# main_ver1_41.net
KiCad netlist of a schematic drawn in EAGLE
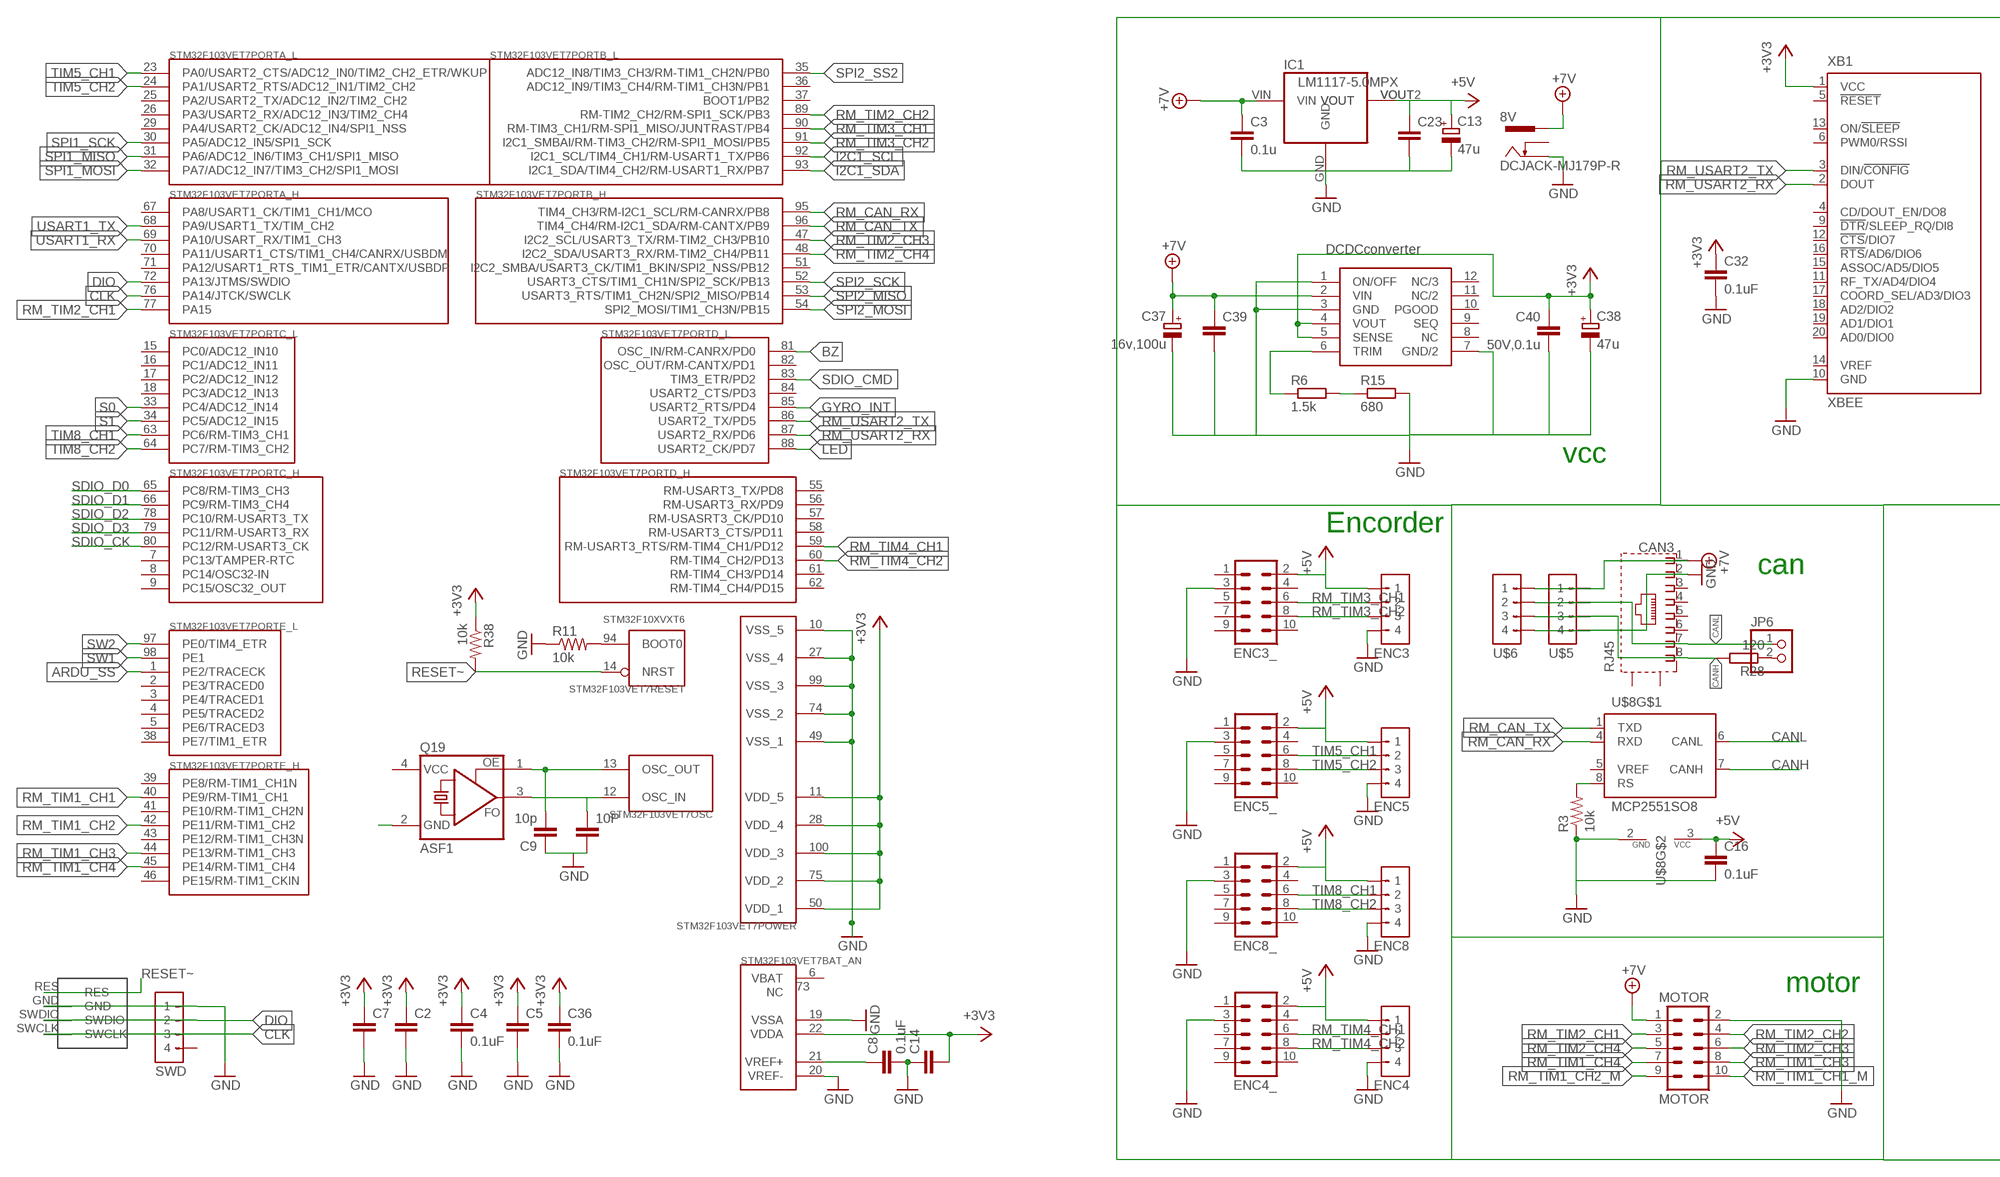
[diagram p0: schematic, sheet 1, part 1 of 2]
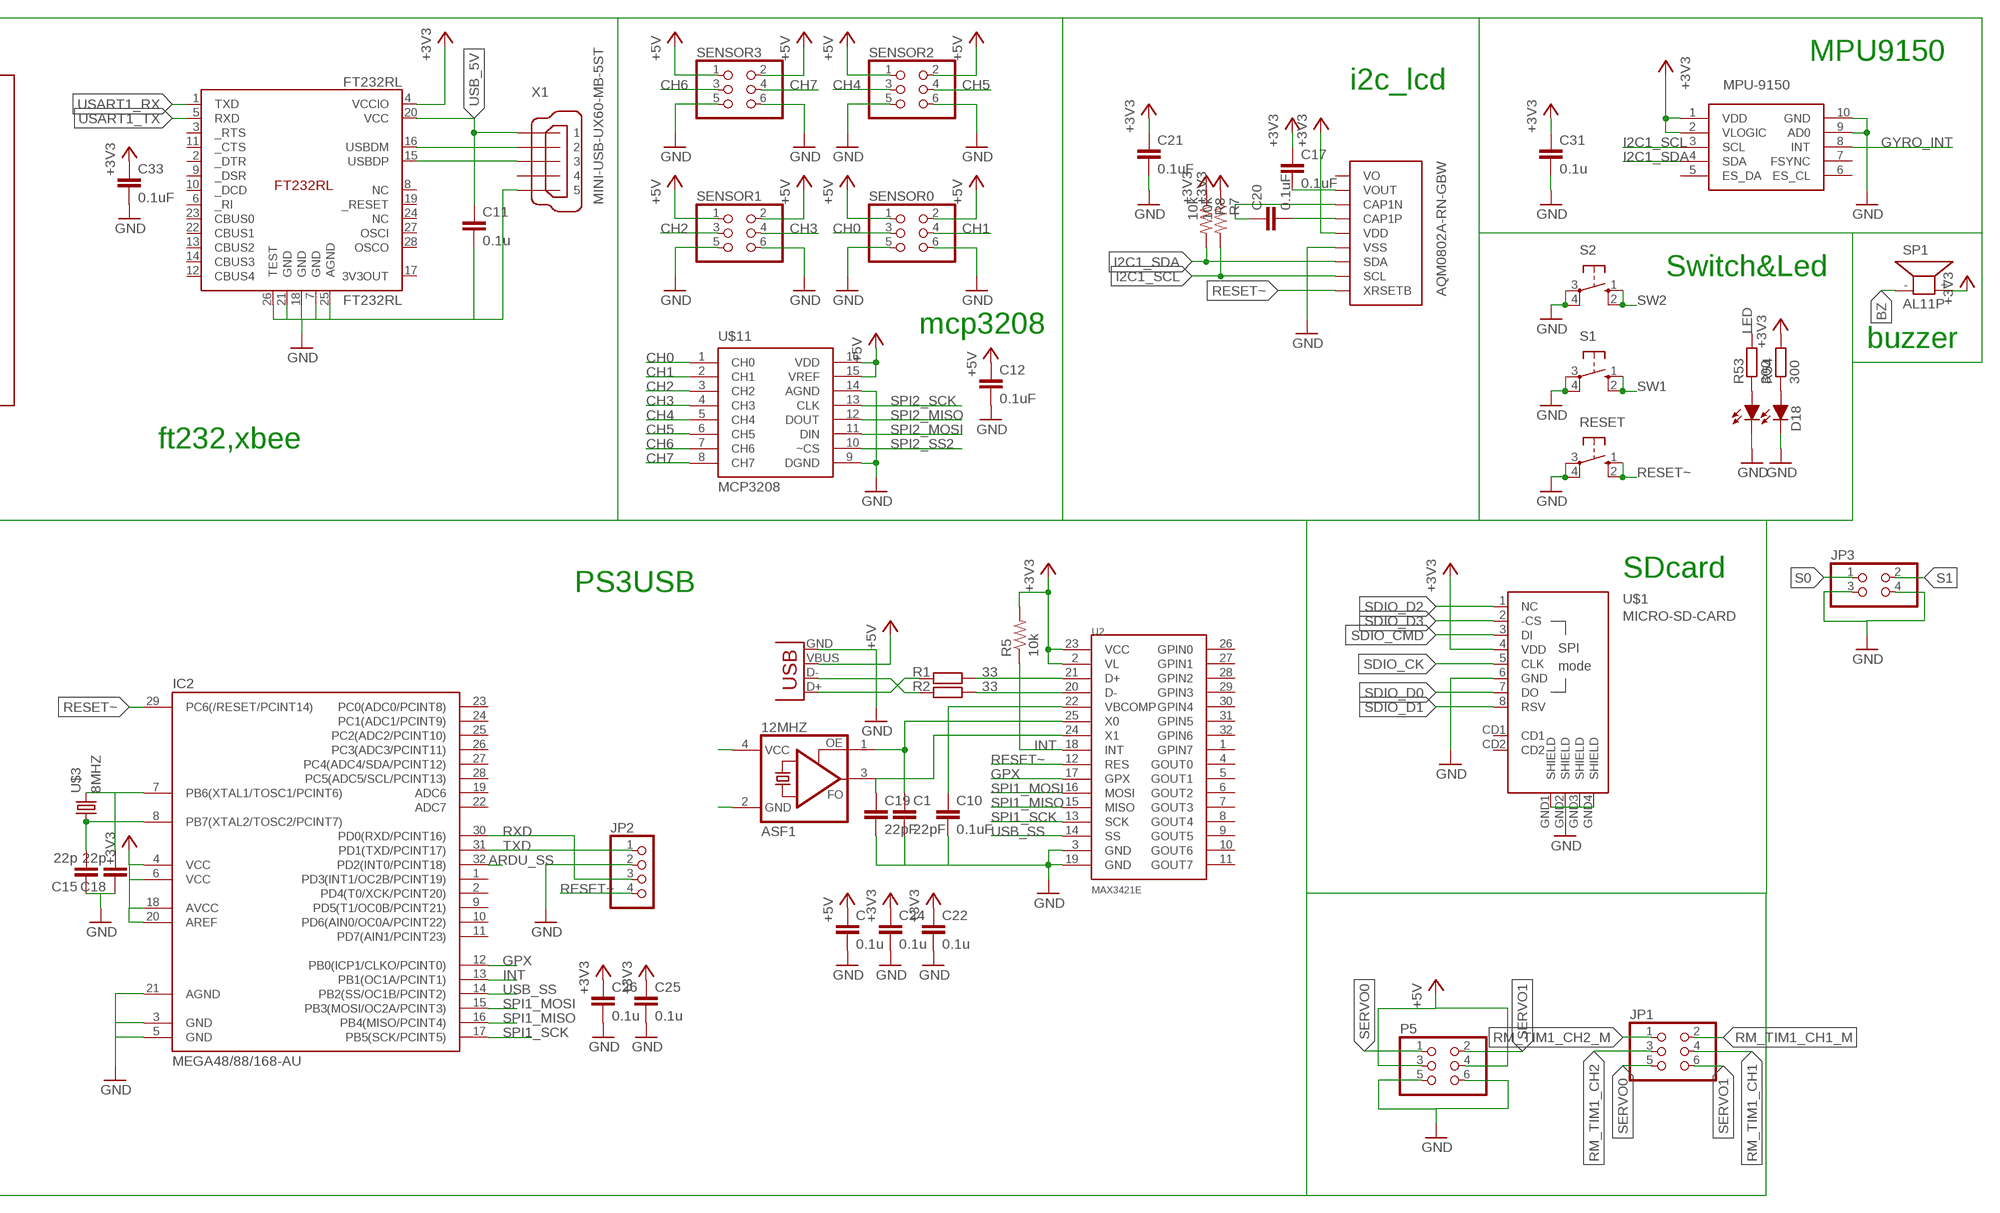
[diagram p1: schematic, sheet 1, part 2 of 2]

(export (version "E")
  (design (tool "Eeschema 10.0.6"))
  (components
    (comp (ref "8V")
      (value "DCJACK-MJ179P-R")
      (footprint "eagle-import:MJ-179P-R")
      (libsource (lib "eagle-import") (part "DCJACK-MJ179P-R"))
    )
    (comp (ref "10P")
      (value "C-EUC0603")
      (footprint "eagle-import:C0603")
      (libsource (lib "eagle-import") (part "C-EUC0603"))
    )
    (comp (ref "12MHZ")
      (value "ASF1")
      (footprint "eagle-import:ASF")
      (libsource (lib "eagle-import") (part "ASF1"))
    )
    (comp (ref "AQM0802A-RN-GBW")
      (value "AQM0802A-RN-GBW")
      (footprint "eagle-import:AQM0802")
      (libsource (lib "eagle-import") (part "AQM0802A-RN-GBW"))
    )
    (comp (ref "C")
      (value "0.1u")
      (footprint "eagle-import:C0603")
      (libsource (lib "eagle-import") (part "resistor_C-EUC0603"))
    )
    (comp (ref "C1")
      (value "22pF")
      (footprint "eagle-import:C0603K")
      (libsource (lib "eagle-import") (part "resistor_C-EUC0603K"))
    )
    (comp (ref "C2")
      (value "C-EUC0603")
      (footprint "eagle-import:C0603")
      (libsource (lib "eagle-import") (part "resistor_C-EUC0603"))
    )
    (comp (ref "C3")
      (value "0.1u")
      (footprint "eagle-import:C0603K")
      (libsource (lib "eagle-import") (part "resistor_C-EUC0603K"))
    )
    (comp (ref "C4")
      (value "0.1uF")
      (footprint "eagle-import:C0603")
      (libsource (lib "eagle-import") (part "resistor_C-EUC0603"))
    )
    (comp (ref "C5")
      (value "C-EUC0603")
      (footprint "eagle-import:C0603")
      (libsource (lib "eagle-import") (part "resistor_C-EUC0603"))
    )
    (comp (ref "C7")
      (value "C-EUC0603")
      (footprint "eagle-import:C0603")
      (libsource (lib "eagle-import") (part "resistor_C-EUC0603"))
    )
    (comp (ref "C8")
      (value "0.1uF")
      (footprint "eagle-import:C0603")
      (libsource (lib "eagle-import") (part "resistor_C-EUC0603"))
    )
    (comp (ref "C9")
      (value "10p")
      (footprint "eagle-import:C0603")
      (libsource (lib "eagle-import") (part "C-EUC0603"))
    )
    (comp (ref "C10")
      (value "0.1uF")
      (footprint "eagle-import:C0603K")
      (libsource (lib "eagle-import") (part "resistor_C-EUC0603K"))
    )
    (comp (ref "C11")
      (value "0.1u")
      (footprint "eagle-import:C0603K")
      (libsource (lib "eagle-import") (part "resistor_C-EUC0603K"))
    )
    (comp (ref "C12")
      (value "0.1uF")
      (footprint "eagle-import:C0603")
      (libsource (lib "eagle-import") (part "resistor_C-EUC0603"))
    )
    (comp (ref "C13")
      (value "47u")
      (footprint "eagle-import:153CLV-0405")
      (libsource (lib "eagle-import") (part "CPOL-EU153CLV-0405"))
    )
    (comp (ref "C14")
      (value "C-EUC0603")
      (footprint "eagle-import:C0603")
      (libsource (lib "eagle-import") (part "resistor_C-EUC0603"))
    )
    (comp (ref "C15")
      (value "22p")
      (footprint "eagle-import:C0603K")
      (libsource (lib "eagle-import") (part "resistor_C-EUC0603K"))
    )
    (comp (ref "C16")
      (value "0.1uF")
      (footprint "eagle-import:C0603")
      (libsource (lib "eagle-import") (part "resistor_C-EUC0603"))
    )
    (comp (ref "C17")
      (value "0.1uF")
      (footprint "eagle-import:C0603")
      (libsource (lib "eagle-import") (part "resistor_C-EUC0603"))
    )
    (comp (ref "C18")
      (value "22p")
      (footprint "eagle-import:C0603K")
      (libsource (lib "eagle-import") (part "resistor_C-EUC0603K"))
    )
    (comp (ref "C19")
      (value "22pF")
      (footprint "eagle-import:C0603K")
      (libsource (lib "eagle-import") (part "resistor_C-EUC0603K"))
    )
    (comp (ref "C20")
      (value "0.1uF")
      (footprint "eagle-import:C0603")
      (libsource (lib "eagle-import") (part "resistor_C-EUC0603"))
    )
    (comp (ref "C21")
      (value "0.1uF")
      (footprint "eagle-import:C0603")
      (libsource (lib "eagle-import") (part "resistor_C-EUC0603"))
    )
    (comp (ref "C22")
      (value "0.1u")
      (footprint "eagle-import:C0603")
      (libsource (lib "eagle-import") (part "resistor_C-EUC0603"))
    )
    (comp (ref "C23")
      (value "C-EUC0603K")
      (footprint "eagle-import:C0603K")
      (libsource (lib "eagle-import") (part "resistor_C-EUC0603K"))
    )
    (comp (ref "C24")
      (value "0.1u")
      (footprint "eagle-import:C0603")
      (libsource (lib "eagle-import") (part "resistor_C-EUC0603"))
    )
    (comp (ref "C25")
      (value "0.1u")
      (footprint "eagle-import:C0603")
      (libsource (lib "eagle-import") (part "resistor_C-EUC0603"))
    )
    (comp (ref "C26")
      (value "0.1u")
      (footprint "eagle-import:C0603")
      (libsource (lib "eagle-import") (part "resistor_C-EUC0603"))
    )
    (comp (ref "C31")
      (value "0.1u")
      (footprint "eagle-import:C0603K")
      (libsource (lib "eagle-import") (part "resistor_C-EUC0603K"))
    )
    (comp (ref "C32")
      (value "0.1uF")
      (footprint "eagle-import:C0603")
      (libsource (lib "eagle-import") (part "resistor_C-EUC0603"))
    )
    (comp (ref "C33")
      (value "0.1uF")
      (footprint "eagle-import:C0603")
      (libsource (lib "eagle-import") (part "resistor_C-EUC0603"))
    )
    (comp (ref "C36")
      (value "0.1uF")
      (footprint "eagle-import:C0603")
      (libsource (lib "eagle-import") (part "resistor_C-EUC0603"))
    )
    (comp (ref "C37")
      (value "16v,100u")
      (footprint "eagle-import:153CLV-0605")
      (libsource (lib "eagle-import") (part "CPOL-EU153CLV-0605"))
    )
    (comp (ref "C38")
      (value "47u")
      (footprint "eagle-import:153CLV-0405")
      (libsource (lib "eagle-import") (part "CPOL-EU153CLV-0405"))
    )
    (comp (ref "C39")
      (value "C-EUC0603K")
      (footprint "eagle-import:C0603K")
      (libsource (lib "eagle-import") (part "resistor_C-EUC0603K"))
    )
    (comp (ref "C40")
      (value "50V,0.1u")
      (footprint "eagle-import:C0603K")
      (libsource (lib "eagle-import") (part "resistor_C-EUC0603K"))
    )
    (comp (ref "CAN3")
      (value "RJ45")
      (footprint "eagle-import:LAN")
      (libsource (lib "eagle-import") (part "RJ45"))
    )
    (comp (ref "D18")
      (value "SEC2XX4")
      (footprint "eagle-import:LED3025")
      (libsource (lib "eagle-import") (part "SEC2XX4"))
    )
    (comp (ref "ENC3")
      (value "CN4-JST-XH-TOP")
      (footprint "eagle-import:JST-B4B-XH-A")
      (libsource (lib "eagle-import") (part "CN4-JST-XH-TOP"))
    )
    (comp (ref "ENC3_")
      (value "ML10L")
      (footprint "eagle-import:ML10L")
      (libsource (lib "eagle-import") (part "con-ml_ML10L"))
    )
    (comp (ref "ENC4")
      (value "CN4-JST-XH-TOP")
      (footprint "eagle-import:JST-B4B-XH-A")
      (libsource (lib "eagle-import") (part "CN4-JST-XH-TOP"))
    )
    (comp (ref "ENC4_")
      (value "ML10L")
      (footprint "eagle-import:ML10L")
      (libsource (lib "eagle-import") (part "con-ml_ML10L"))
    )
    (comp (ref "ENC5")
      (value "CN4-JST-XH-TOP")
      (footprint "eagle-import:JST-B4B-XH-A")
      (libsource (lib "eagle-import") (part "CN4-JST-XH-TOP"))
    )
    (comp (ref "ENC5_")
      (value "ML10L")
      (footprint "eagle-import:ML10L")
      (libsource (lib "eagle-import") (part "con-ml_ML10L"))
    )
    (comp (ref "ENC8")
      (value "CN4-JST-XH-TOP")
      (footprint "eagle-import:JST-B4B-XH-A")
      (libsource (lib "eagle-import") (part "CN4-JST-XH-TOP"))
    )
    (comp (ref "ENC8_")
      (value "ML10L")
      (footprint "eagle-import:ML10L")
      (libsource (lib "eagle-import") (part "con-ml_ML10L"))
    )
    (comp (ref "FT232RL")
      (value "FT232RL")
      (footprint "eagle-import:SSOP-28")
      (libsource (lib "eagle-import") (part "FT232RL"))
    )
    (comp (ref "IC1")
      (value "LM1117-5.0MPX")
      (footprint "eagle-import:SOT223")
      (libsource (lib "eagle-import") (part "LM1117IMP-5.0"))
    )
    (comp (ref "IC2")
      (value "MEGA48/88/168-AU")
      (footprint "eagle-import:TQFP32-08")
      (libsource (lib "eagle-import") (part "MEGA48/88/168-AU"))
    )
    (comp (ref "JP1")
      (value "PINHD-2X3")
      (footprint "eagle-import:2X03")
      (libsource (lib "eagle-import") (part "PINHD-2X3"))
    )
    (comp (ref "JP2")
      (value "PINHD-1X4")
      (footprint "eagle-import:1X04")
      (libsource (lib "eagle-import") (part "PINHD-1X4"))
    )
    (comp (ref "JP3")
      (value "PINHD-2X2/90")
      (footprint "eagle-import:2X02_90")
      (libsource (lib "eagle-import") (part "PINHD-2X2/90"))
    )
    (comp (ref "JP6")
      (value "PINHD-1X2")
      (footprint "eagle-import:1X02")
      (libsource (lib "eagle-import") (part "PINHD-1X2"))
    )
    (comp (ref "MOTOR")
      (value "MOTOR")
      (footprint "eagle-import:ML10L")
      (libsource (lib "eagle-import") (part "ML10L"))
    )
    (comp (ref "MPU9150")
      (value "MPU-9150")
      (footprint "eagle-import:MPU-9150")
      (libsource (lib "eagle-import") (part "MPU-9150"))
    )
    (comp (ref "P5")
      (value "PINHD-2X3/90")
      (footprint "eagle-import:2X03_90")
      (libsource (lib "eagle-import") (part "PINHD-2X3/90"))
    )
    (comp (ref "Q19")
      (value "ASF1")
      (footprint "eagle-import:ASF")
      (libsource (lib "eagle-import") (part "ASF1"))
    )
    (comp (ref "R1")
      (value "33")
      (footprint "eagle-import:R0603")
      (libsource (lib "eagle-import") (part "R-EU_R0603"))
    )
    (comp (ref "R2")
      (value "33")
      (footprint "eagle-import:R0603")
      (libsource (lib "eagle-import") (part "R-EU_R0603"))
    )
    (comp (ref "R3")
      (value "10k")
      (footprint "eagle-import:R0603")
      (libsource (lib "eagle-import") (part "R-US_R0603"))
    )
    (comp (ref "R5")
      (value "10k")
      (footprint "eagle-import:R0603")
      (libsource (lib "eagle-import") (part "R-US_R0603"))
    )
    (comp (ref "R6")
      (value "1.5k")
      (footprint "eagle-import:R0603")
      (libsource (lib "eagle-import") (part "R-EU_R0603"))
    )
    (comp (ref "R7")
      (value "10k")
      (footprint "eagle-import:R0603")
      (libsource (lib "eagle-import") (part "R-US_R0603"))
    )
    (comp (ref "R8")
      (value "10k")
      (footprint "eagle-import:R0603")
      (libsource (lib "eagle-import") (part "R-US_R0603"))
    )
    (comp (ref "R11")
      (value "10k")
      (footprint "eagle-import:R0603")
      (libsource (lib "eagle-import") (part "R-US_R0603"))
    )
    (comp (ref "R15")
      (value "680")
      (footprint "eagle-import:R0603")
      (libsource (lib "eagle-import") (part "R-EU_R0603"))
    )
    (comp (ref "R28")
      (value "120")
      (footprint "eagle-import:R0603")
      (libsource (lib "eagle-import") (part "R-EU_R0603"))
    )
    (comp (ref "R38")
      (value "10k")
      (footprint "eagle-import:R0603")
      (libsource (lib "eagle-import") (part "R-US_R0603"))
    )
    (comp (ref "R53")
      (value "300")
      (footprint "eagle-import:R0603")
      (libsource (lib "eagle-import") (part "R-EU_R0603"))
    )
    (comp (ref "R54")
      (value "300")
      (footprint "eagle-import:R0603")
      (libsource (lib "eagle-import") (part "R-EU_R0603"))
    )
    (comp (ref "RESET")
      (value "10-XX")
      (footprint "eagle-import:B3F-10XX")
      (fields (field (name "MPN") "B3F-1000"))
      (libsource (lib "eagle-import") (part "10-XX"))
    )
    (comp (ref "S1")
      (value "10-XX")
      (footprint "eagle-import:B3F-10XX")
      (fields (field (name "MPN") "B3F-1000"))
      (libsource (lib "eagle-import") (part "10-XX"))
    )
    (comp (ref "S2")
      (value "10-XX")
      (footprint "eagle-import:B3F-10XX")
      (fields (field (name "MPN") "B3F-1000"))
      (libsource (lib "eagle-import") (part "10-XX"))
    )
    (comp (ref "SENSOR0")
      (value "PINHD-2X3/90")
      (footprint "eagle-import:2X03_90")
      (libsource (lib "eagle-import") (part "PINHD-2X3/90"))
    )
    (comp (ref "SENSOR1")
      (value "PINHD-2X3/90")
      (footprint "eagle-import:2X03_90")
      (libsource (lib "eagle-import") (part "PINHD-2X3/90"))
    )
    (comp (ref "SENSOR2")
      (value "PINHD-2X3/90")
      (footprint "eagle-import:2X03_90")
      (libsource (lib "eagle-import") (part "PINHD-2X3/90"))
    )
    (comp (ref "SENSOR3")
      (value "PINHD-2X3/90")
      (footprint "eagle-import:2X03_90")
      (libsource (lib "eagle-import") (part "PINHD-2X3/90"))
    )
    (comp (ref "SP1")
      (value "AL11P")
      (footprint "eagle-import:AL11P")
      (libsource (lib "eagle-import") (part "AL11P"))
    )
    (comp (ref "STM32F103VET7")
      (value "STM32F10XVXT6")
      (footprint "eagle-import:LQFP100")
      (libsource (lib "eagle-import") (part "STM32F10XVXT6"))
    )
    (comp (ref "SWD")
      (value "TOP_TYPE_4PIN")
      (footprint "eagle-import:TOP_TYPE_4PIN")
      (libsource (lib "eagle-import") (part "TOP_TYPE_4PIN"))
    )
    (comp (ref "U$1")
      (value "MICRO-SD-CARD")
      (footprint "eagle-import:DM3AT-SF-PEJ")
      (libsource (lib "eagle-import") (part "MICRO-SD-CARD"))
    )
    (comp (ref "U$2")
      (value "OKL-T/6-W12N")
      (footprint "eagle-import:OKL-T_6-W12")
      (libsource (lib "eagle-import") (part "OKL-T/6-W12N"))
    )
    (comp (ref "U$3")
      (value "8MHZ")
      (footprint "eagle-import:8MHZ_C")
      (libsource (lib "eagle-import") (part "8MHZ"))
    )
    (comp (ref "U$5")
      (value "S4B-XH-SM4-TB")
      (footprint "eagle-import:S4B-XH-SM4-TB")
      (libsource (lib "eagle-import") (part "S4B-XH-SM4-TB"))
    )
    (comp (ref "U$6")
      (value "S4B-XH-SM4-TB")
      (footprint "eagle-import:S4B-XH-SM4-TB")
      (libsource (lib "eagle-import") (part "S4B-XH-SM4-TB"))
    )
    (comp (ref "U$7")
      (value "STRINK")
      (footprint "eagle-import:STLINK")
      (libsource (lib "eagle-import") (part "STRINK"))
    )
    (comp (ref "U$8")
      (value "MCP2551SO8")
      (footprint "eagle-import:SO08")
      (libsource (lib "eagle-import") (part "MCP2551SO8"))
    )
    (comp (ref "U$11")
      (value "MCP3208")
      (footprint "eagle-import:SO16")
      (libsource (lib "eagle-import") (part "MCP3208"))
    )
    (comp (ref "U2")
      (value "MAX3421E")
      (footprint "eagle-import:TQFP32-5MM")
      (libsource (lib "eagle-import") (part "MAX3421ESMD"))
    )
    (comp (ref "X1")
      (value "MINI-USB-UX60-MB-5ST")
      (footprint "eagle-import:UX60-MB-5ST")
      (libsource (lib "eagle-import") (part "MINI-USB-UX60-MB-5ST"))
    )
    (comp (ref "X2")
      (value "USB_")
      (footprint "eagle-import:USB-A-S-SILK-FEMALE")
      (libsource (lib "eagle-import") (part "USB_"))
    )
    (comp (ref "XB1")
      (value "XBEE")
      (footprint "eagle-import:XBEE")
      (libsource (lib "eagle-import") (part "XBEE"))
    )
  )
  (nets
    (net (code "1") (name "+3V3") (class "Default")
      (node (ref "AQM0802A-RN-GBW") (pin "P$5") (pinfunction "VDD_P$5") (pintype "bidirectional"))
      (node (ref "C14") (pin "2") (pinfunction "2_2") (pintype "passive"))
      (node (ref "C17") (pin "1") (pinfunction "1_1") (pintype "passive"))
      (node (ref "C2") (pin "1") (pinfunction "1_1") (pintype "passive"))
      (node (ref "C21") (pin "1") (pinfunction "1_1") (pintype "passive"))
      (node (ref "C22") (pin "1") (pinfunction "1_1") (pintype "passive"))
      (node (ref "C24") (pin "1") (pinfunction "1_1") (pintype "passive"))
      (node (ref "C25") (pin "1") (pinfunction "1_1") (pintype "passive"))
      (node (ref "C26") (pin "1") (pinfunction "1_1") (pintype "passive"))
      (node (ref "C31") (pin "1") (pinfunction "1_1") (pintype "passive"))
      (node (ref "C32") (pin "1") (pinfunction "1_1") (pintype "passive"))
      (node (ref "C33") (pin "1") (pinfunction "1_1") (pintype "passive"))
      (node (ref "C36") (pin "1") (pinfunction "1_1") (pintype "passive"))
      (node (ref "C38") (pin "+") (pinfunction "+_+") (pintype "passive"))
      (node (ref "C4") (pin "1") (pinfunction "1_1") (pintype "passive"))
      (node (ref "C40") (pin "1") (pinfunction "1_1") (pintype "passive"))
      (node (ref "C5") (pin "1") (pinfunction "1_1") (pintype "passive"))
      (node (ref "C7") (pin "1") (pinfunction "1_1") (pintype "passive"))
      (node (ref "FT232RL") (pin "4") (pinfunction "VCCIO_4") (pintype "power_in"))
      (node (ref "IC2") (pin "18") (pinfunction "AVCC_18") (pintype "passive"))
      (node (ref "IC2") (pin "20") (pinfunction "AREF_20") (pintype "passive"))
      (node (ref "IC2") (pin "4") (pinfunction "VCC_4") (pintype "power_in"))
      (node (ref "IC2") (pin "6") (pinfunction "VCC_6") (pintype "power_in"))
      (node (ref "MPU9150") (pin "1") (pinfunction "VDD_1") (pintype "bidirectional"))
      (node (ref "MPU9150") (pin "2") (pinfunction "VLOGIC_2") (pintype "bidirectional"))
      (node (ref "R38") (pin "1") (pinfunction "1_1") (pintype "passive"))
      (node (ref "R5") (pin "2") (pinfunction "2_2") (pintype "passive"))
      (node (ref "R54") (pin "2") (pinfunction "2_2") (pintype "passive"))
      (node (ref "R7") (pin "1") (pinfunction "1_1") (pintype "passive"))
      (node (ref "R8") (pin "1") (pinfunction "1_1") (pintype "passive"))
      (node (ref "SP1") (pin "+") (pinfunction "2_+") (pintype "passive"))
      (node (ref "STM32F103VET7") (pin "100") (pinfunction "VDD_3_100") (pintype "power_in"))
      (node (ref "STM32F103VET7") (pin "11") (pinfunction "VDD_5_11") (pintype "power_in"))
      (node (ref "STM32F103VET7") (pin "22") (pinfunction "VDDA_22") (pintype "power_in"))
      (node (ref "STM32F103VET7") (pin "28") (pinfunction "VDD_4_28") (pintype "power_in"))
      (node (ref "STM32F103VET7") (pin "50") (pinfunction "VDD_1_50") (pintype "power_in"))
      (node (ref "STM32F103VET7") (pin "75") (pinfunction "VDD_2_75") (pintype "power_in"))
      (node (ref "U$1") (pin "4") (pinfunction "VDD_4") (pintype "bidirectional"))
      (node (ref "U$2") (pin "4") (pinfunction "VOUT_4") (pintype "bidirectional"))
      (node (ref "U$2") (pin "5") (pinfunction "SENSE_5") (pintype "bidirectional"))
      (node (ref "U2") (pin "2") (pinfunction "VL_2") (pintype "bidirectional"))
      (node (ref "U2") (pin "23") (pinfunction "VCC_23") (pintype "bidirectional"))
      (node (ref "XB1") (pin "1") (pinfunction "VCC_1") (pintype "power_in"))
    )
    (net (code "2") (name "+5V") (class "Default")
      (node (ref "C") (pin "1") (pinfunction "1_1") (pintype "passive"))
      (node (ref "C12") (pin "1") (pinfunction "1_1") (pintype "passive"))
      (node (ref "C13") (pin "+") (pinfunction "+_+") (pintype "passive"))
      (node (ref "C16") (pin "1") (pinfunction "1_1") (pintype "passive"))
      (node (ref "C23") (pin "1") (pinfunction "1_1") (pintype "passive"))
      (node (ref "ENC3") (pin "1") (pinfunction "1_1") (pintype "passive"))
      (node (ref "ENC3_") (pin "2") (pinfunction "2_2") (pintype "passive"))
      (node (ref "ENC4") (pin "1") (pinfunction "1_1") (pintype "passive"))
      (node (ref "ENC4_") (pin "2") (pinfunction "2_2") (pintype "passive"))
      (node (ref "ENC5") (pin "1") (pinfunction "1_1") (pintype "passive"))
      (node (ref "ENC5_") (pin "2") (pinfunction "2_2") (pintype "passive"))
      (node (ref "ENC8") (pin "1") (pinfunction "1_1") (pintype "passive"))
      (node (ref "ENC8_") (pin "2") (pinfunction "2_2") (pintype "passive"))
      (node (ref "IC1") (pin "VOUT") (pinfunction "VOUT_VOUT") (pintype "output"))
      (node (ref "IC1") (pin "VOUT2") (pinfunction "VOUT_VOUT2") (pintype "output"))
      (node (ref "P5") (pin "3") (pinfunction "3_3") (pintype "passive"))
      (node (ref "P5") (pin "4") (pinfunction "4_4") (pintype "passive"))
      (node (ref "SENSOR0") (pin "1") (pinfunction "1_1") (pintype "passive"))
      (node (ref "SENSOR0") (pin "2") (pinfunction "2_2") (pintype "passive"))
      (node (ref "SENSOR1") (pin "1") (pinfunction "1_1") (pintype "passive"))
      (node (ref "SENSOR1") (pin "2") (pinfunction "2_2") (pintype "passive"))
      (node (ref "SENSOR2") (pin "1") (pinfunction "1_1") (pintype "passive"))
      (node (ref "SENSOR2") (pin "2") (pinfunction "2_2") (pintype "passive"))
      (node (ref "SENSOR3") (pin "1") (pinfunction "1_1") (pintype "passive"))
      (node (ref "SENSOR3") (pin "2") (pinfunction "2_2") (pintype "passive"))
      (node (ref "U$11") (pin "15") (pinfunction "VREF_15") (pintype "bidirectional"))
      (node (ref "U$11") (pin "16") (pinfunction "VDD_16") (pintype "bidirectional"))
      (node (ref "U$8") (pin "3") (pinfunction "VCC_3") (pintype "power_in"))
      (node (ref "X2") (pin "VBUS") (pinfunction "VBUS_VBUS") (pintype "bidirectional"))
    )
    (net (code "3") (name "+7V") (class "Default")
      (node (ref "8V") (pin "1") (pinfunction "1_1") (pintype "passive"))
      (node (ref "C3") (pin "1") (pinfunction "1_1") (pintype "passive"))
      (node (ref "C37") (pin "+") (pinfunction "+_+") (pintype "passive"))
      (node (ref "C39") (pin "1") (pinfunction "1_1") (pintype "passive"))
      (node (ref "CAN3") (pin "1") (pinfunction "1_1") (pintype "passive"))
      (node (ref "IC1") (pin "VIN") (pinfunction "VIN_VIN") (pintype "input"))
      (node (ref "MOTOR") (pin "1") (pinfunction "1_1") (pintype "passive"))
      (node (ref "U$2") (pin "2") (pinfunction "VIN_2") (pintype "bidirectional"))
      (node (ref "U$5") (pin "1") (pinfunction "1_1") (pintype "passive"))
      (node (ref "U$6") (pin "1") (pinfunction "1_1") (pintype "passive"))
    )
    (net (code "4") (name "/CH0") (class "Default")
      (node (ref "SENSOR0") (pin "3") (pinfunction "3_3") (pintype "passive"))
      (node (ref "U$11") (pin "1") (pinfunction "CH0_1") (pintype "bidirectional"))
    )
    (net (code "5") (name "/CH1") (class "Default")
      (node (ref "SENSOR0") (pin "4") (pinfunction "4_4") (pintype "passive"))
      (node (ref "U$11") (pin "2") (pinfunction "CH1_2") (pintype "bidirectional"))
    )
    (net (code "6") (name "/CH2") (class "Default")
      (node (ref "SENSOR1") (pin "3") (pinfunction "3_3") (pintype "passive"))
      (node (ref "U$11") (pin "3") (pinfunction "CH2_3") (pintype "bidirectional"))
    )
    (net (code "7") (name "/CH3") (class "Default")
      (node (ref "SENSOR1") (pin "4") (pinfunction "4_4") (pintype "passive"))
      (node (ref "U$11") (pin "4") (pinfunction "CH3_4") (pintype "bidirectional"))
    )
    (net (code "8") (name "/CH4") (class "Default")
      (node (ref "SENSOR2") (pin "3") (pinfunction "3_3") (pintype "passive"))
      (node (ref "U$11") (pin "5") (pinfunction "CH4_5") (pintype "bidirectional"))
    )
    (net (code "9") (name "/CH5") (class "Default")
      (node (ref "SENSOR2") (pin "4") (pinfunction "4_4") (pintype "passive"))
      (node (ref "U$11") (pin "6") (pinfunction "CH5_6") (pintype "bidirectional"))
    )
    (net (code "10") (name "/CH6") (class "Default")
      (node (ref "SENSOR3") (pin "3") (pinfunction "3_3") (pintype "passive"))
      (node (ref "U$11") (pin "7") (pinfunction "CH6_7") (pintype "bidirectional"))
    )
    (net (code "11") (name "/CH7") (class "Default")
      (node (ref "SENSOR3") (pin "4") (pinfunction "4_4") (pintype "passive"))
      (node (ref "U$11") (pin "8") (pinfunction "CH7_8") (pintype "bidirectional"))
    )
    (net (code "12") (name "/GPX") (class "Default")
      (node (ref "IC2") (pin "12") (pinfunction "PB0(ICP1/CLKO/PCINT0)_12") (pintype "bidirectional"))
      (node (ref "U2") (pin "17") (pinfunction "GPX_17") (pintype "bidirectional"))
    )
    (net (code "13") (name "/INT") (class "Default")
      (node (ref "IC2") (pin "13") (pinfunction "PB1(OC1A/PCINT1)_13") (pintype "bidirectional"))
      (node (ref "R5") (pin "1") (pinfunction "1_1") (pintype "passive"))
      (node (ref "U2") (pin "18") (pinfunction "INT_18") (pintype "bidirectional"))
    )
    (net (code "14") (name "/RESET~{}") (class "Default")
      (node (ref "AQM0802A-RN-GBW") (pin "P$9") (pinfunction "XRSETB_P$9") (pintype "bidirectional"))
      (node (ref "IC2") (pin "29") (pinfunction "PC6(/RESET/PCINT14)_29") (pintype "bidirectional"))
      (node (ref "JP2") (pin "4") (pinfunction "4_4") (pintype "passive"))
      (node (ref "R38") (pin "2") (pinfunction "2_2") (pintype "passive"))
      (node (ref "RESET") (pin "1") (pinfunction "S_1") (pintype "passive"))
      (node (ref "RESET") (pin "2") (pinfunction "S1_2") (pintype "passive"))
      (node (ref "STM32F103VET7") (pin "14") (pinfunction "NRST_14") (pintype "input"))
      (node (ref "U$7") (pin "RES") (pinfunction "RES_RES") (pintype "bidirectional"))
      (node (ref "U2") (pin "12") (pinfunction "RES_12") (pintype "bidirectional"))
    )
    (net (code "15") (name "/RXD") (class "Default")
      (node (ref "IC2") (pin "30") (pinfunction "PD0(RXD/PCINT16)_30") (pintype "bidirectional"))
      (node (ref "JP2") (pin "3") (pinfunction "3_3") (pintype "passive"))
    )
    (net (code "16") (name "/TXD") (class "Default")
      (node (ref "IC2") (pin "31") (pinfunction "PD1(TXD/PCINT17)_31") (pintype "bidirectional"))
      (node (ref "JP2") (pin "1") (pinfunction "1_1") (pintype "passive"))
    )
    (net (code "17") (name "/USB_SS") (class "Default")
      (node (ref "IC2") (pin "14") (pinfunction "PB2(SS/OC1B/PCINT2)_14") (pintype "bidirectional"))
      (node (ref "U2") (pin "14") (pinfunction "SS_14") (pintype "bidirectional"))
    )
    (net (code "18") (name "/VBAT") (class "Default")
      (node (ref "STM32F103VET7") (pin "6") (pinfunction "VBAT_6") (pintype "power_in"))
    )
    (net (code "19") (name "/VCC") (class "Default")
      (node (ref "Q19") (pin "4") (pinfunction "VCC_4") (pintype "power_in"))
    )
    (net (code "20") (name "ARDU_SS") (class "Default")
      (node (ref "IC2") (pin "32") (pinfunction "PD2(INT0/PCINT18)_32") (pintype "bidirectional"))
      (node (ref "STM32F103VET7") (pin "1") (pinfunction "PE2/TRACECK_1") (pintype "bidirectional"))
    )
    (net (code "21") (name "BZ") (class "Default")
      (node (ref "SP1") (pin "-") (pinfunction "1_-") (pintype "passive"))
      (node (ref "STM32F103VET7") (pin "81") (pinfunction "OSC_IN/RM-CANRX/PD0_81") (pintype "bidirectional"))
    )
    (net (code "22") (name "CANH") (class "Default")
      (node (ref "CAN3") (pin "8") (pinfunction "8_8") (pintype "passive"))
      (node (ref "R28") (pin "2") (pinfunction "2_2") (pintype "passive"))
      (node (ref "U$5") (pin "3") (pinfunction "3_3") (pintype "passive"))
      (node (ref "U$6") (pin "3") (pinfunction "3_3") (pintype "passive"))
      (node (ref "U$8") (pin "7") (pinfunction "CANH_7") (pintype "bidirectional"))
    )
    (net (code "23") (name "CANL") (class "Default")
      (node (ref "CAN3") (pin "7") (pinfunction "7_7") (pintype "passive"))
      (node (ref "JP6") (pin "1") (pinfunction "1_1") (pintype "passive"))
      (node (ref "U$5") (pin "2") (pinfunction "2_2") (pintype "passive"))
      (node (ref "U$6") (pin "2") (pinfunction "2_2") (pintype "passive"))
      (node (ref "U$8") (pin "6") (pinfunction "CANL_6") (pintype "bidirectional"))
    )
    (net (code "24") (name "CLK") (class "Default")
      (node (ref "STM32F103VET7") (pin "76") (pinfunction "PA14/JTCK/SWCLK_76") (pintype "bidirectional"))
      (node (ref "SWD") (pin "3") (pinfunction "3_3") (pintype "passive"))
      (node (ref "U$7") (pin "SWCLK") (pinfunction "SWCLK_SWCLK") (pintype "bidirectional"))
    )
    (net (code "25") (name "DIO") (class "Default")
      (node (ref "STM32F103VET7") (pin "72") (pinfunction "PA13/JTMS/SWDIO_72") (pintype "bidirectional"))
      (node (ref "SWD") (pin "2") (pinfunction "2_2") (pintype "passive"))
      (node (ref "U$7") (pin "SWDIO") (pinfunction "SWDIO_SWDIO") (pintype "bidirectional"))
    )
    (net (code "26") (name "GND") (class "Default")
      (node (ref "10P") (pin "2") (pinfunction "2_2") (pintype "passive"))
      (node (ref "8V") (pin "2") (pinfunction "2_2") (pintype "passive"))
      (node (ref "AQM0802A-RN-GBW") (pin "P$6") (pinfunction "VSS_P$6") (pintype "bidirectional"))
      (node (ref "C") (pin "2") (pinfunction "2_2") (pintype "passive"))
      (node (ref "C1") (pin "2") (pinfunction "2_2") (pintype "passive"))
      (node (ref "C10") (pin "2") (pinfunction "2_2") (pintype "passive"))
      (node (ref "C11") (pin "2") (pinfunction "2_2") (pintype "passive"))
      (node (ref "C12") (pin "2") (pinfunction "2_2") (pintype "passive"))
      (node (ref "C13") (pin "-") (pinfunction "-_-") (pintype "passive"))
      (node (ref "C14") (pin "1") (pinfunction "1_1") (pintype "passive"))
      (node (ref "C15") (pin "1") (pinfunction "1_1") (pintype "passive"))
      (node (ref "C16") (pin "2") (pinfunction "2_2") (pintype "passive"))
      (node (ref "C18") (pin "1") (pinfunction "1_1") (pintype "passive"))
      (node (ref "C19") (pin "2") (pinfunction "2_2") (pintype "passive"))
      (node (ref "C2") (pin "2") (pinfunction "2_2") (pintype "passive"))
      (node (ref "C21") (pin "2") (pinfunction "2_2") (pintype "passive"))
      (node (ref "C22") (pin "2") (pinfunction "2_2") (pintype "passive"))
      (node (ref "C23") (pin "2") (pinfunction "2_2") (pintype "passive"))
      (node (ref "C24") (pin "2") (pinfunction "2_2") (pintype "passive"))
      (node (ref "C25") (pin "2") (pinfunction "2_2") (pintype "passive"))
      (node (ref "C26") (pin "2") (pinfunction "2_2") (pintype "passive"))
      (node (ref "C3") (pin "2") (pinfunction "2_2") (pintype "passive"))
      (node (ref "C31") (pin "2") (pinfunction "2_2") (pintype "passive"))
      (node (ref "C32") (pin "2") (pinfunction "2_2") (pintype "passive"))
      (node (ref "C33") (pin "2") (pinfunction "2_2") (pintype "passive"))
      (node (ref "C36") (pin "2") (pinfunction "2_2") (pintype "passive"))
      (node (ref "C37") (pin "-") (pinfunction "-_-") (pintype "passive"))
      (node (ref "C38") (pin "-") (pinfunction "-_-") (pintype "passive"))
      (node (ref "C39") (pin "2") (pinfunction "2_2") (pintype "passive"))
      (node (ref "C4") (pin "2") (pinfunction "2_2") (pintype "passive"))
      (node (ref "C40") (pin "2") (pinfunction "2_2") (pintype "passive"))
      (node (ref "C5") (pin "2") (pinfunction "2_2") (pintype "passive"))
      (node (ref "C7") (pin "2") (pinfunction "2_2") (pintype "passive"))
      (node (ref "C8") (pin "2") (pinfunction "2_2") (pintype "passive"))
      (node (ref "C9") (pin "1") (pinfunction "1_1") (pintype "passive"))
      (node (ref "CAN3") (pin "2") (pinfunction "2_2") (pintype "passive"))
      (node (ref "D18") (pin "1") (pinfunction "C0_1") (pintype "passive"))
      (node (ref "D18") (pin "2") (pinfunction "C1_2") (pintype "passive"))
      (node (ref "ENC3") (pin "4") (pinfunction "4_4") (pintype "passive"))
      (node (ref "ENC3_") (pin "3") (pinfunction "3_3") (pintype "passive"))
      (node (ref "ENC4") (pin "4") (pinfunction "4_4") (pintype "passive"))
      (node (ref "ENC4_") (pin "3") (pinfunction "3_3") (pintype "passive"))
      (node (ref "ENC5") (pin "4") (pinfunction "4_4") (pintype "passive"))
      (node (ref "ENC5_") (pin "3") (pinfunction "3_3") (pintype "passive"))
      (node (ref "ENC8") (pin "4") (pinfunction "4_4") (pintype "passive"))
      (node (ref "ENC8_") (pin "3") (pinfunction "3_3") (pintype "passive"))
      (node (ref "FT232RL") (pin "18") (pinfunction "GND_18") (pintype "power_in"))
      (node (ref "FT232RL") (pin "21") (pinfunction "GND_21") (pintype "power_in"))
      (node (ref "FT232RL") (pin "25") (pinfunction "AGND_25") (pintype "power_in"))
      (node (ref "FT232RL") (pin "26") (pinfunction "TEST_26") (pintype "bidirectional"))
      (node (ref "FT232RL") (pin "7") (pinfunction "GND_7") (pintype "power_in"))
      (node (ref "IC1") (pin "GND") (pinfunction "GND_GND") (pintype "power_in"))
      (node (ref "IC2") (pin "21") (pinfunction "AGND_21") (pintype "power_in"))
      (node (ref "IC2") (pin "3") (pinfunction "GND_3") (pintype "power_in"))
      (node (ref "IC2") (pin "5") (pinfunction "GND_5") (pintype "power_in"))
      (node (ref "JP2") (pin "2") (pinfunction "2_2") (pintype "passive"))
      (node (ref "JP3") (pin "3") (pinfunction "3_3") (pintype "passive"))
      (node (ref "JP3") (pin "4") (pinfunction "4_4") (pintype "passive"))
      (node (ref "MOTOR") (pin "2") (pinfunction "2_2") (pintype "passive"))
      (node (ref "MPU9150") (pin "10") (pinfunction "GND_10") (pintype "bidirectional"))
      (node (ref "MPU9150") (pin "9") (pinfunction "AD0_9") (pintype "bidirectional"))
      (node (ref "P5") (pin "5") (pinfunction "5_5") (pintype "passive"))
      (node (ref "P5") (pin "6") (pinfunction "6_6") (pintype "passive"))
      (node (ref "R11") (pin "1") (pinfunction "1_1") (pintype "passive"))
      (node (ref "R15") (pin "2") (pinfunction "2_2") (pintype "passive"))
      (node (ref "R3") (pin "1") (pinfunction "1_1") (pintype "passive"))
      (node (ref "RESET") (pin "3") (pinfunction "P_3") (pintype "passive"))
      (node (ref "RESET") (pin "4") (pinfunction "P1_4") (pintype "passive"))
      (node (ref "S1") (pin "3") (pinfunction "P_3") (pintype "passive"))
      (node (ref "S1") (pin "4") (pinfunction "P1_4") (pintype "passive"))
      (node (ref "S2") (pin "3") (pinfunction "P_3") (pintype "passive"))
      (node (ref "S2") (pin "4") (pinfunction "P1_4") (pintype "passive"))
      (node (ref "SENSOR0") (pin "5") (pinfunction "5_5") (pintype "passive"))
      (node (ref "SENSOR0") (pin "6") (pinfunction "6_6") (pintype "passive"))
      (node (ref "SENSOR1") (pin "5") (pinfunction "5_5") (pintype "passive"))
      (node (ref "SENSOR1") (pin "6") (pinfunction "6_6") (pintype "passive"))
      (node (ref "SENSOR2") (pin "5") (pinfunction "5_5") (pintype "passive"))
      (node (ref "SENSOR2") (pin "6") (pinfunction "6_6") (pintype "passive"))
      (node (ref "SENSOR3") (pin "5") (pinfunction "5_5") (pintype "passive"))
      (node (ref "SENSOR3") (pin "6") (pinfunction "6_6") (pintype "passive"))
      (node (ref "STM32F103VET7") (pin "10") (pinfunction "VSS_5_10") (pintype "power_in"))
      (node (ref "STM32F103VET7") (pin "19") (pinfunction "VSSA_19") (pintype "power_in"))
      (node (ref "STM32F103VET7") (pin "20") (pinfunction "VREF-_20") (pintype "input"))
      (node (ref "STM32F103VET7") (pin "27") (pinfunction "VSS_4_27") (pintype "power_in"))
      (node (ref "STM32F103VET7") (pin "49") (pinfunction "VSS_1_49") (pintype "power_in"))
      (node (ref "STM32F103VET7") (pin "74") (pinfunction "VSS_2_74") (pintype "power_in"))
      (node (ref "STM32F103VET7") (pin "99") (pinfunction "VSS_3_99") (pintype "power_in"))
      (node (ref "SWD") (pin "1") (pinfunction "1_1") (pintype "passive"))
      (node (ref "U$1") (pin "6") (pinfunction "GND_6") (pintype "bidirectional"))
      (node (ref "U$1") (pin "GND1") (pinfunction "SHIELD_GND1") (pintype "bidirectional"))
      (node (ref "U$1") (pin "GND2") (pinfunction "SHIELD_GND2") (pintype "bidirectional"))
      (node (ref "U$1") (pin "GND3") (pinfunction "SHIELD_GND3") (pintype "bidirectional"))
      (node (ref "U$1") (pin "GND4") (pinfunction "SHIELD_GND4") (pintype "bidirectional"))
      (node (ref "U$11") (pin "14") (pinfunction "AGND_14") (pintype "bidirectional"))
      (node (ref "U$11") (pin "9") (pinfunction "DGND_9") (pintype "bidirectional"))
      (node (ref "U$2") (pin "1") (pinfunction "ON/OFF_1") (pintype "bidirectional"))
      (node (ref "U$2") (pin "3") (pinfunction "GND_3") (pintype "bidirectional"))
      (node (ref "U$2") (pin "7") (pinfunction "GND/2_7") (pintype "bidirectional"))
      (node (ref "U$5") (pin "4") (pinfunction "4_4") (pintype "passive"))
      (node (ref "U$6") (pin "4") (pinfunction "4_4") (pintype "passive"))
      (node (ref "U$7") (pin "GND") (pinfunction "GND_GND") (pintype "bidirectional"))
      (node (ref "U$8") (pin "2") (pinfunction "GND_2") (pintype "power_in"))
      (node (ref "U2") (pin "19") (pinfunction "GND_19") (pintype "bidirectional"))
      (node (ref "U2") (pin "3") (pinfunction "GND_3") (pintype "bidirectional"))
      (node (ref "X1") (pin "5") (pinfunction "5_5") (pintype "input"))
      (node (ref "X2") (pin "GND") (pinfunction "GND_GND") (pintype "bidirectional"))
      (node (ref "XB1") (pin "10") (pinfunction "GND_10") (pintype "power_in"))
    )
    (net (code "27") (name "GYRO_INT") (class "Default")
      (node (ref "MPU9150") (pin "8") (pinfunction "INT_8") (pintype "bidirectional"))
      (node (ref "STM32F103VET7") (pin "85") (pinfunction "USART2_RTS/PD4_85") (pintype "bidirectional"))
    )
    (net (code "28") (name "I2C1_SCL") (class "Default")
      (node (ref "AQM0802A-RN-GBW") (pin "P$8") (pinfunction "SCL_P$8") (pintype "bidirectional"))
      (node (ref "MPU9150") (pin "3") (pinfunction "SCL_3") (pintype "bidirectional"))
      (node (ref "R7") (pin "2") (pinfunction "2_2") (pintype "passive"))
      (node (ref "STM32F103VET7") (pin "92") (pinfunction "I2C1_SCL/TIM4_CH1/RM-USART1_TX/PB6_92") (pintype "bidirectional"))
    )
    (net (code "29") (name "I2C1_SDA") (class "Default")
      (node (ref "AQM0802A-RN-GBW") (pin "P$7") (pinfunction "SDA_P$7") (pintype "bidirectional"))
      (node (ref "MPU9150") (pin "4") (pinfunction "SDA_4") (pintype "bidirectional"))
      (node (ref "R8") (pin "2") (pinfunction "2_2") (pintype "passive"))
      (node (ref "STM32F103VET7") (pin "93") (pinfunction "I2C1_SDA/TIM4_CH2/RM-USART1_RX/PB7_93") (pintype "bidirectional"))
    )
    (net (code "30") (name "LED") (class "Default")
      (node (ref "R53") (pin "2") (pinfunction "2_2") (pintype "passive"))
      (node (ref "STM32F103VET7") (pin "88") (pinfunction "USART2_CK/PD7_88") (pintype "bidirectional"))
    )
    (net (code "31") (name "Net-(12MHZ-FO)") (class "Default")
      (node (ref "12MHZ") (pin "3") (pinfunction "FO_3") (pintype "output"))
      (node (ref "C19") (pin "1") (pinfunction "1_1") (pintype "passive"))
      (node (ref "U2") (pin "24") (pinfunction "X1_24") (pintype "bidirectional"))
    )
    (net (code "32") (name "Net-(12MHZ-OE)") (class "Default")
      (node (ref "12MHZ") (pin "1") (pinfunction "OE_1") (pintype "input"))
      (node (ref "C1") (pin "1") (pinfunction "1_1") (pintype "passive"))
      (node (ref "U2") (pin "25") (pinfunction "X0_25") (pintype "bidirectional"))
    )
    (net (code "33") (name "Net-(AQM0802A-RN-GBW-CAP1N)") (class "Default")
      (node (ref "AQM0802A-RN-GBW") (pin "P$3") (pinfunction "CAP1N_P$3") (pintype "bidirectional"))
      (node (ref "C20") (pin "1") (pinfunction "1_1") (pintype "passive"))
    )
    (net (code "34") (name "Net-(AQM0802A-RN-GBW-CAP1P)") (class "Default")
      (node (ref "AQM0802A-RN-GBW") (pin "P$4") (pinfunction "CAP1P_P$4") (pintype "bidirectional"))
      (node (ref "C20") (pin "2") (pinfunction "2_2") (pintype "passive"))
    )
    (net (code "35") (name "Net-(AQM0802A-RN-GBW-VOUT)") (class "Default")
      (node (ref "AQM0802A-RN-GBW") (pin "P$2") (pinfunction "VOUT_P$2") (pintype "bidirectional"))
      (node (ref "C17") (pin "2") (pinfunction "2_2") (pintype "passive"))
    )
    (net (code "36") (name "Net-(D18-A0)") (class "Default")
      (node (ref "D18") (pin "4") (pinfunction "A0_4") (pintype "passive"))
      (node (ref "R54") (pin "1") (pinfunction "1_1") (pintype "passive"))
    )
    (net (code "37") (name "Net-(D18-A1)") (class "Default")
      (node (ref "D18") (pin "3") (pinfunction "A1_3") (pintype "passive"))
      (node (ref "R53") (pin "1") (pinfunction "1_1") (pintype "passive"))
    )
    (net (code "38") (name "Net-(FT232RL-USBDM)") (class "Default")
      (node (ref "FT232RL") (pin "16") (pinfunction "USBDM_16") (pintype "bidirectional"))
      (node (ref "X1") (pin "2") (pinfunction "2_2") (pintype "input"))
    )
    (net (code "39") (name "Net-(FT232RL-USBDP)") (class "Default")
      (node (ref "FT232RL") (pin "15") (pinfunction "USBDP_15") (pintype "bidirectional"))
      (node (ref "X1") (pin "3") (pinfunction "3_3") (pintype "input"))
    )
    (net (code "40") (name "Net-(IC2-PB6(XTAL1{slash}TOSC1{slash}PCINT6))") (class "Default")
      (node (ref "C18") (pin "2") (pinfunction "2_2") (pintype "passive"))
      (node (ref "IC2") (pin "7") (pinfunction "PB6(XTAL1/TOSC1/PCINT6)_7") (pintype "bidirectional"))
      (node (ref "U$3") (pin "P$2") (pinfunction "2_P$2") (pintype "passive"))
    )
    (net (code "41") (name "Net-(IC2-PB7(XTAL2{slash}TOSC2{slash}PCINT7))") (class "Default")
      (node (ref "C15") (pin "2") (pinfunction "2_2") (pintype "passive"))
      (node (ref "IC2") (pin "8") (pinfunction "PB7(XTAL2/TOSC2/PCINT7)_8") (pintype "bidirectional"))
      (node (ref "U$3") (pin "P$1") (pinfunction "1_P$1") (pintype "passive"))
    )
    (net (code "42") (name "Net-(JP6-Pad2)") (class "Default")
      (node (ref "JP6") (pin "2") (pinfunction "2_2") (pintype "passive"))
      (node (ref "R28") (pin "1") (pinfunction "1_1") (pintype "passive"))
    )
    (net (code "43") (name "Net-(Q19-FO)") (class "Default")
      (node (ref "10P") (pin "1") (pinfunction "1_1") (pintype "passive"))
      (node (ref "Q19") (pin "3") (pinfunction "FO_3") (pintype "output"))
      (node (ref "STM32F103VET7") (pin "12") (pinfunction "OSC_IN_12") (pintype "input"))
    )
    (net (code "44") (name "Net-(Q19-OE)") (class "Default")
      (node (ref "C9") (pin "2") (pinfunction "2_2") (pintype "passive"))
      (node (ref "Q19") (pin "1") (pinfunction "OE_1") (pintype "input"))
      (node (ref "STM32F103VET7") (pin "13") (pinfunction "OSC_OUT_13") (pintype "output"))
    )
    (net (code "45") (name "Net-(R1-Pad2)") (class "Default")
      (node (ref "R1") (pin "2") (pinfunction "2_2") (pintype "passive"))
      (node (ref "X2") (pin "D+") (pinfunction "D+_D+") (pintype "bidirectional"))
    )
    (net (code "46") (name "Net-(R2-Pad2)") (class "Default")
      (node (ref "R2") (pin "2") (pinfunction "2_2") (pintype "passive"))
      (node (ref "X2") (pin "D-") (pinfunction "D-_D-") (pintype "bidirectional"))
    )
    (net (code "47") (name "Net-(R15-Pad1)") (class "Default")
      (node (ref "R15") (pin "1") (pinfunction "1_1") (pintype "passive"))
      (node (ref "R6") (pin "2") (pinfunction "2_2") (pintype "passive"))
    )
    (net (code "48") (name "Net-(STM32F103VET7A-VREF+)") (class "Default")
      (node (ref "C8") (pin "1") (pinfunction "1_1") (pintype "passive"))
      (node (ref "STM32F103VET7") (pin "21") (pinfunction "VREF+_21") (pintype "input"))
    )
    (net (code "49") (name "Net-(STM32F103VET7N-BOOT0)") (class "Default")
      (node (ref "R11") (pin "2") (pinfunction "2_2") (pintype "passive"))
      (node (ref "STM32F103VET7") (pin "94") (pinfunction "BOOT0_94") (pintype "input"))
    )
    (net (code "50") (name "Net-(U$2-TRIM)") (class "Default")
      (node (ref "R6") (pin "1") (pinfunction "1_1") (pintype "passive"))
      (node (ref "U$2") (pin "6") (pinfunction "TRIM_6") (pintype "bidirectional"))
    )
    (net (code "51") (name "Net-(U$8A-RS)") (class "Default")
      (node (ref "R3") (pin "2") (pinfunction "2_2") (pintype "passive"))
      (node (ref "U$8") (pin "8") (pinfunction "RS_8") (pintype "bidirectional"))
    )
    (net (code "52") (name "Net-(U2-D+)") (class "Default")
      (node (ref "R1") (pin "1") (pinfunction "1_1") (pintype "passive"))
      (node (ref "U2") (pin "21") (pinfunction "D+_21") (pintype "bidirectional"))
    )
    (net (code "53") (name "Net-(U2-D-)") (class "Default")
      (node (ref "R2") (pin "1") (pinfunction "1_1") (pintype "passive"))
      (node (ref "U2") (pin "20") (pinfunction "D-_20") (pintype "bidirectional"))
    )
    (net (code "54") (name "Net-(U2-VBCOMP)") (class "Default")
      (node (ref "C10") (pin "1") (pinfunction "1_1") (pintype "passive"))
      (node (ref "U2") (pin "22") (pinfunction "VBCOMP_22") (pintype "bidirectional"))
    )
    (net (code "55") (name "RM_CAN_RX") (class "Default")
      (node (ref "STM32F103VET7") (pin "95") (pinfunction "TIM4_CH3/RM-I2C1_SCL/RM-CANRX/PB8_95") (pintype "bidirectional"))
      (node (ref "U$8") (pin "4") (pinfunction "RXD_4") (pintype "bidirectional"))
    )
    (net (code "56") (name "RM_CAN_TX") (class "Default")
      (node (ref "STM32F103VET7") (pin "96") (pinfunction "TIM4_CH4/RM-I2C1_SDA/RM-CANTX/PB9_96") (pintype "bidirectional"))
      (node (ref "U$8") (pin "1") (pinfunction "TXD_1") (pintype "bidirectional"))
    )
    (net (code "57") (name "RM_TIM1_CH1") (class "Default")
      (node (ref "JP1") (pin "4") (pinfunction "4_4") (pintype "passive"))
      (node (ref "STM32F103VET7") (pin "40") (pinfunction "PE9/RM-TIM1_CH1_40") (pintype "bidirectional"))
    )
    (net (code "58") (name "RM_TIM1_CH1_M") (class "Default")
      (node (ref "JP1") (pin "2") (pinfunction "2_2") (pintype "passive"))
      (node (ref "MOTOR") (pin "10") (pinfunction "10_10") (pintype "passive"))
    )
    (net (code "59") (name "RM_TIM1_CH2") (class "Default")
      (node (ref "JP1") (pin "3") (pinfunction "3_3") (pintype "passive"))
      (node (ref "STM32F103VET7") (pin "42") (pinfunction "PE11/RM-TIM1_CH2_42") (pintype "bidirectional"))
    )
    (net (code "60") (name "RM_TIM1_CH2_M") (class "Default")
      (node (ref "JP1") (pin "1") (pinfunction "1_1") (pintype "passive"))
      (node (ref "MOTOR") (pin "9") (pinfunction "9_9") (pintype "passive"))
    )
    (net (code "61") (name "RM_TIM1_CH3") (class "Default")
      (node (ref "MOTOR") (pin "8") (pinfunction "8_8") (pintype "passive"))
      (node (ref "STM32F103VET7") (pin "44") (pinfunction "PE13/RM-TIM1_CH3_44") (pintype "bidirectional"))
    )
    (net (code "62") (name "RM_TIM1_CH4") (class "Default")
      (node (ref "MOTOR") (pin "7") (pinfunction "7_7") (pintype "passive"))
      (node (ref "STM32F103VET7") (pin "45") (pinfunction "PE14/RM-TIM1_CH4_45") (pintype "bidirectional"))
    )
    (net (code "63") (name "RM_TIM2_CH1") (class "Default")
      (node (ref "MOTOR") (pin "3") (pinfunction "3_3") (pintype "passive"))
      (node (ref "STM32F103VET7") (pin "77") (pinfunction "PA15_77") (pintype "bidirectional"))
    )
    (net (code "64") (name "RM_TIM2_CH2") (class "Default")
      (node (ref "MOTOR") (pin "4") (pinfunction "4_4") (pintype "passive"))
      (node (ref "STM32F103VET7") (pin "89") (pinfunction "RM-TIM2_CH2/RM-SPI1_SCK/PB3_89") (pintype "bidirectional"))
    )
    (net (code "65") (name "RM_TIM2_CH3") (class "Default")
      (node (ref "MOTOR") (pin "6") (pinfunction "6_6") (pintype "passive"))
      (node (ref "STM32F103VET7") (pin "47") (pinfunction "I2C2_SCL/USART3_TX/RM-TIM2_CH3/PB10_47") (pintype "bidirectional"))
    )
    (net (code "66") (name "RM_TIM2_CH4") (class "Default")
      (node (ref "MOTOR") (pin "5") (pinfunction "5_5") (pintype "passive"))
      (node (ref "STM32F103VET7") (pin "48") (pinfunction "I2C2_SDA/USART3_RX/RM-TIM2_CH4/PB11_48") (pintype "bidirectional"))
    )
    (net (code "67") (name "RM_TIM3_CH1") (class "Default")
      (node (ref "ENC3") (pin "2") (pinfunction "2_2") (pintype "passive"))
      (node (ref "ENC3_") (pin "6") (pinfunction "6_6") (pintype "passive"))
      (node (ref "STM32F103VET7") (pin "90") (pinfunction "RM-TIM3_CH1/RM-SPI1_MISO/JUNTRAST/PB4_90") (pintype "bidirectional"))
    )
    (net (code "68") (name "RM_TIM3_CH2") (class "Default")
      (node (ref "ENC3") (pin "3") (pinfunction "3_3") (pintype "passive"))
      (node (ref "ENC3_") (pin "8") (pinfunction "8_8") (pintype "passive"))
      (node (ref "STM32F103VET7") (pin "91") (pinfunction "I2C1_SMBAI/RM-TIM3_CH2/RM-SPI1_MOSI/PB5_91") (pintype "bidirectional"))
    )
    (net (code "69") (name "RM_TIM4_CH1") (class "Default")
      (node (ref "ENC4") (pin "2") (pinfunction "2_2") (pintype "passive"))
      (node (ref "ENC4_") (pin "6") (pinfunction "6_6") (pintype "passive"))
      (node (ref "STM32F103VET7") (pin "59") (pinfunction "RM-USART3_RTS/RM-TIM4_CH1/PD12_59") (pintype "bidirectional"))
    )
    (net (code "70") (name "RM_TIM4_CH2") (class "Default")
      (node (ref "ENC4") (pin "3") (pinfunction "3_3") (pintype "passive"))
      (node (ref "ENC4_") (pin "8") (pinfunction "8_8") (pintype "passive"))
      (node (ref "STM32F103VET7") (pin "60") (pinfunction "RM-TIM4_CH2/PD13_60") (pintype "bidirectional"))
    )
    (net (code "71") (name "RM_USART2_RX") (class "Default")
      (node (ref "STM32F103VET7") (pin "87") (pinfunction "USART2_RX/PD6_87") (pintype "bidirectional"))
      (node (ref "XB1") (pin "2") (pinfunction "DOUT_2") (pintype "output"))
    )
    (net (code "72") (name "RM_USART2_TX") (class "Default")
      (node (ref "STM32F103VET7") (pin "86") (pinfunction "USART2_TX/PD5_86") (pintype "bidirectional"))
      (node (ref "XB1") (pin "3") (pinfunction "DIN/~{CONFIG}_3") (pintype "input"))
    )
    (net (code "73") (name "S0") (class "Default")
      (node (ref "JP3") (pin "1") (pinfunction "1_1") (pintype "passive"))
      (node (ref "STM32F103VET7") (pin "33") (pinfunction "PC4/ADC12_IN14_33") (pintype "bidirectional"))
    )
    (net (code "74") (name "S1") (class "Default")
      (node (ref "JP3") (pin "2") (pinfunction "2_2") (pintype "passive"))
      (node (ref "STM32F103VET7") (pin "34") (pinfunction "PC5/ADC12_IN15_34") (pintype "bidirectional"))
    )
    (net (code "75") (name "SDIO_CK") (class "Default")
      (node (ref "STM32F103VET7") (pin "80") (pinfunction "PC12/RM-USART3_CK_80") (pintype "bidirectional"))
      (node (ref "U$1") (pin "5") (pinfunction "CLK_5") (pintype "bidirectional"))
    )
    (net (code "76") (name "SDIO_CMD") (class "Default")
      (node (ref "STM32F103VET7") (pin "83") (pinfunction "TIM3_ETR/PD2_83") (pintype "bidirectional"))
      (node (ref "U$1") (pin "3") (pinfunction "DI_3") (pintype "bidirectional"))
    )
    (net (code "77") (name "SDIO_D0") (class "Default")
      (node (ref "STM32F103VET7") (pin "65") (pinfunction "PC8/RM-TIM3_CH3_65") (pintype "bidirectional"))
      (node (ref "U$1") (pin "7") (pinfunction "DO_7") (pintype "bidirectional"))
    )
    (net (code "78") (name "SDIO_D1") (class "Default")
      (node (ref "STM32F103VET7") (pin "66") (pinfunction "PC9/RM-TIM3_CH4_66") (pintype "bidirectional"))
      (node (ref "U$1") (pin "8") (pinfunction "RSV_8") (pintype "bidirectional"))
    )
    (net (code "79") (name "SDIO_D2") (class "Default")
      (node (ref "STM32F103VET7") (pin "78") (pinfunction "PC10/RM-USART3_TX_78") (pintype "bidirectional"))
      (node (ref "U$1") (pin "1") (pinfunction "NC_1") (pintype "bidirectional"))
    )
    (net (code "80") (name "SDIO_D3") (class "Default")
      (node (ref "STM32F103VET7") (pin "79") (pinfunction "PC11/RM-USART3_RX_79") (pintype "bidirectional"))
      (node (ref "U$1") (pin "2") (pinfunction "-CS_2") (pintype "bidirectional"))
    )
    (net (code "81") (name "SERVO0") (class "Default")
      (node (ref "JP1") (pin "5") (pinfunction "5_5") (pintype "passive"))
      (node (ref "P5") (pin "1") (pinfunction "1_1") (pintype "passive"))
    )
    (net (code "82") (name "SERVO1") (class "Default")
      (node (ref "JP1") (pin "6") (pinfunction "6_6") (pintype "passive"))
      (node (ref "P5") (pin "2") (pinfunction "2_2") (pintype "passive"))
    )
    (net (code "83") (name "SPI1_MISO") (class "Default")
      (node (ref "IC2") (pin "16") (pinfunction "PB4(MISO/PCINT4)_16") (pintype "bidirectional"))
      (node (ref "STM32F103VET7") (pin "31") (pinfunction "PA6/ADC12_IN6/TIM3_CH1/SPI1_MISO_31") (pintype "bidirectional"))
      (node (ref "U2") (pin "15") (pinfunction "MISO_15") (pintype "bidirectional"))
    )
    (net (code "84") (name "SPI1_MOSI") (class "Default")
      (node (ref "IC2") (pin "15") (pinfunction "PB3(MOSI/OC2A/PCINT3)_15") (pintype "bidirectional"))
      (node (ref "STM32F103VET7") (pin "32") (pinfunction "PA7/ADC12_IN7/TIM3_CH2/SPI1_MOSI_32") (pintype "bidirectional"))
      (node (ref "U2") (pin "16") (pinfunction "MOSI_16") (pintype "bidirectional"))
    )
    (net (code "85") (name "SPI1_SCK") (class "Default")
      (node (ref "IC2") (pin "17") (pinfunction "PB5(SCK/PCINT5)_17") (pintype "bidirectional"))
      (node (ref "STM32F103VET7") (pin "30") (pinfunction "PA5/ADC12_IN5/SPI1_SCK_30") (pintype "bidirectional"))
      (node (ref "U2") (pin "13") (pinfunction "SCK_13") (pintype "bidirectional"))
    )
    (net (code "86") (name "SPI2_MISO") (class "Default")
      (node (ref "STM32F103VET7") (pin "53") (pinfunction "USART3_RTS/TIM1_CH2N/SPI2_MISO/PB14_53") (pintype "bidirectional"))
      (node (ref "U$11") (pin "12") (pinfunction "DOUT_12") (pintype "bidirectional"))
    )
    (net (code "87") (name "SPI2_MOSI") (class "Default")
      (node (ref "STM32F103VET7") (pin "54") (pinfunction "SPI2_MOSI/TIM1_CH3N/PB15_54") (pintype "bidirectional"))
      (node (ref "U$11") (pin "11") (pinfunction "DIN_11") (pintype "bidirectional"))
    )
    (net (code "88") (name "SPI2_SCK") (class "Default")
      (node (ref "STM32F103VET7") (pin "52") (pinfunction "USART3_CTS/TIM1_CH1N/SPI2_SCK/PB13_52") (pintype "bidirectional"))
      (node (ref "U$11") (pin "13") (pinfunction "CLK_13") (pintype "bidirectional"))
    )
    (net (code "89") (name "SPI2_SS2") (class "Default")
      (node (ref "STM32F103VET7") (pin "35") (pinfunction "ADC12_IN8/TIM3_CH3/RM-TIM1_CH2N/PB0_35") (pintype "bidirectional"))
      (node (ref "U$11") (pin "10") (pinfunction "~{CS}_10") (pintype "bidirectional"))
    )
    (net (code "90") (name "SW1") (class "Default")
      (node (ref "S1") (pin "1") (pinfunction "S_1") (pintype "passive"))
      (node (ref "S1") (pin "2") (pinfunction "S1_2") (pintype "passive"))
      (node (ref "STM32F103VET7") (pin "98") (pinfunction "PE1_98") (pintype "bidirectional"))
    )
    (net (code "91") (name "SW2") (class "Default")
      (node (ref "S2") (pin "1") (pinfunction "S_1") (pintype "passive"))
      (node (ref "S2") (pin "2") (pinfunction "S1_2") (pintype "passive"))
      (node (ref "STM32F103VET7") (pin "97") (pinfunction "PE0/TIM4_ETR_97") (pintype "bidirectional"))
    )
    (net (code "92") (name "TIM5_CH1") (class "Default")
      (node (ref "ENC5") (pin "2") (pinfunction "2_2") (pintype "passive"))
      (node (ref "ENC5_") (pin "6") (pinfunction "6_6") (pintype "passive"))
      (node (ref "STM32F103VET7") (pin "23") (pinfunction "PA0/USART2_CTS/ADC12_IN0/TIM2_CH2_ETR/WKUP_23") (pintype "bidirectional"))
    )
    (net (code "93") (name "TIM5_CH2") (class "Default")
      (node (ref "ENC5") (pin "3") (pinfunction "3_3") (pintype "passive"))
      (node (ref "ENC5_") (pin "8") (pinfunction "8_8") (pintype "passive"))
      (node (ref "STM32F103VET7") (pin "24") (pinfunction "PA1/USART2_RTS/ADC12_IN1/TIM2_CH2_24") (pintype "bidirectional"))
    )
    (net (code "94") (name "TIM8_CH1") (class "Default")
      (node (ref "ENC8") (pin "2") (pinfunction "2_2") (pintype "passive"))
      (node (ref "ENC8_") (pin "6") (pinfunction "6_6") (pintype "passive"))
      (node (ref "STM32F103VET7") (pin "63") (pinfunction "PC6/RM-TIM3_CH1_63") (pintype "bidirectional"))
    )
    (net (code "95") (name "TIM8_CH2") (class "Default")
      (node (ref "ENC8") (pin "3") (pinfunction "3_3") (pintype "passive"))
      (node (ref "ENC8_") (pin "8") (pinfunction "8_8") (pintype "passive"))
      (node (ref "STM32F103VET7") (pin "64") (pinfunction "PC7/RM-TIM3_CH2_64") (pintype "bidirectional"))
    )
    (net (code "96") (name "USART1_RX") (class "Default")
      (node (ref "FT232RL") (pin "1") (pinfunction "TXD_1") (pintype "output"))
      (node (ref "STM32F103VET7") (pin "69") (pinfunction "PA10/USART_RX/TIM1_CH3_69") (pintype "bidirectional"))
    )
    (net (code "97") (name "USART1_TX") (class "Default")
      (node (ref "FT232RL") (pin "5") (pinfunction "RXD_5") (pintype "input"))
      (node (ref "STM32F103VET7") (pin "68") (pinfunction "PA9/USART1_TX/TIM_CH2_68") (pintype "bidirectional"))
    )
    (net (code "98") (name "USB_5V") (class "Default")
      (node (ref "C11") (pin "1") (pinfunction "1_1") (pintype "passive"))
      (node (ref "FT232RL") (pin "20") (pinfunction "VCC_20") (pintype "power_in"))
      (node (ref "X1") (pin "1") (pinfunction "1_1") (pintype "input"))
    )
    (net (code "99") (name "unconnected-(8V-Pad3)") (class "Default")
      (node (ref "8V") (pin "3") (pinfunction "3_3") (pintype "passive"))
    )
    (net (code "100") (name "unconnected-(12MHZ-GND-Pad2)") (class "Default")
      (node (ref "12MHZ") (pin "2") (pinfunction "GND_2") (pintype "power_in"))
    )
    (net (code "101") (name "unconnected-(12MHZ-VCC-Pad4)") (class "Default")
      (node (ref "12MHZ") (pin "4") (pinfunction "VCC_4") (pintype "power_in"))
    )
    (net (code "102") (name "unconnected-(AQM0802A-RN-GBW-VO-PadP$1)") (class "Default")
      (node (ref "AQM0802A-RN-GBW") (pin "P$1") (pinfunction "VO_P$1") (pintype "bidirectional"))
    )
    (net (code "103") (name "unconnected-(CAN3-Pad3)") (class "Default")
      (node (ref "CAN3") (pin "3") (pinfunction "3_3") (pintype "passive"))
    )
    (net (code "104") (name "unconnected-(CAN3-Pad4)") (class "Default")
      (node (ref "CAN3") (pin "4") (pinfunction "4_4") (pintype "passive"))
    )
    (net (code "105") (name "unconnected-(CAN3-Pad5)") (class "Default")
      (node (ref "CAN3") (pin "5") (pinfunction "5_5") (pintype "passive"))
    )
    (net (code "106") (name "unconnected-(CAN3-Pad6)") (class "Default")
      (node (ref "CAN3") (pin "6") (pinfunction "6_6") (pintype "passive"))
    )
    (net (code "107") (name "unconnected-(CAN3-S-PadP$11)") (class "Default")
      (node (ref "CAN3") (pin "P$11") (pinfunction "S_P$11") (pintype "passive"))
    )
    (net (code "108") (name "unconnected-(CAN3-S-PadP$12)") (class "Default")
      (node (ref "CAN3") (pin "P$12") (pinfunction "S_P$12") (pintype "passive"))
    )
    (net (code "109") (name "unconnected-(ENC3_-Pad1)") (class "Default")
      (node (ref "ENC3_") (pin "1") (pinfunction "1_1") (pintype "passive"))
    )
    (net (code "110") (name "unconnected-(ENC3_-Pad4)") (class "Default")
      (node (ref "ENC3_") (pin "4") (pinfunction "4_4") (pintype "passive"))
    )
    (net (code "111") (name "unconnected-(ENC3_-Pad5)") (class "Default")
      (node (ref "ENC3_") (pin "5") (pinfunction "5_5") (pintype "passive"))
    )
    (net (code "112") (name "unconnected-(ENC3_-Pad7)") (class "Default")
      (node (ref "ENC3_") (pin "7") (pinfunction "7_7") (pintype "passive"))
    )
    (net (code "113") (name "unconnected-(ENC3_-Pad9)") (class "Default")
      (node (ref "ENC3_") (pin "9") (pinfunction "9_9") (pintype "passive"))
    )
    (net (code "114") (name "unconnected-(ENC3_-Pad10)") (class "Default")
      (node (ref "ENC3_") (pin "10") (pinfunction "10_10") (pintype "passive"))
    )
    (net (code "115") (name "unconnected-(ENC4_-Pad1)") (class "Default")
      (node (ref "ENC4_") (pin "1") (pinfunction "1_1") (pintype "passive"))
    )
    (net (code "116") (name "unconnected-(ENC4_-Pad4)") (class "Default")
      (node (ref "ENC4_") (pin "4") (pinfunction "4_4") (pintype "passive"))
    )
    (net (code "117") (name "unconnected-(ENC4_-Pad5)") (class "Default")
      (node (ref "ENC4_") (pin "5") (pinfunction "5_5") (pintype "passive"))
    )
    (net (code "118") (name "unconnected-(ENC4_-Pad7)") (class "Default")
      (node (ref "ENC4_") (pin "7") (pinfunction "7_7") (pintype "passive"))
    )
    (net (code "119") (name "unconnected-(ENC4_-Pad9)") (class "Default")
      (node (ref "ENC4_") (pin "9") (pinfunction "9_9") (pintype "passive"))
    )
    (net (code "120") (name "unconnected-(ENC4_-Pad10)") (class "Default")
      (node (ref "ENC4_") (pin "10") (pinfunction "10_10") (pintype "passive"))
    )
    (net (code "121") (name "unconnected-(ENC5_-Pad1)") (class "Default")
      (node (ref "ENC5_") (pin "1") (pinfunction "1_1") (pintype "passive"))
    )
    (net (code "122") (name "unconnected-(ENC5_-Pad4)") (class "Default")
      (node (ref "ENC5_") (pin "4") (pinfunction "4_4") (pintype "passive"))
    )
    (net (code "123") (name "unconnected-(ENC5_-Pad5)") (class "Default")
      (node (ref "ENC5_") (pin "5") (pinfunction "5_5") (pintype "passive"))
    )
    (net (code "124") (name "unconnected-(ENC5_-Pad7)") (class "Default")
      (node (ref "ENC5_") (pin "7") (pinfunction "7_7") (pintype "passive"))
    )
    (net (code "125") (name "unconnected-(ENC5_-Pad9)") (class "Default")
      (node (ref "ENC5_") (pin "9") (pinfunction "9_9") (pintype "passive"))
    )
    (net (code "126") (name "unconnected-(ENC5_-Pad10)") (class "Default")
      (node (ref "ENC5_") (pin "10") (pinfunction "10_10") (pintype "passive"))
    )
    (net (code "127") (name "unconnected-(ENC8_-Pad1)") (class "Default")
      (node (ref "ENC8_") (pin "1") (pinfunction "1_1") (pintype "passive"))
    )
    (net (code "128") (name "unconnected-(ENC8_-Pad4)") (class "Default")
      (node (ref "ENC8_") (pin "4") (pinfunction "4_4") (pintype "passive"))
    )
    (net (code "129") (name "unconnected-(ENC8_-Pad5)") (class "Default")
      (node (ref "ENC8_") (pin "5") (pinfunction "5_5") (pintype "passive"))
    )
    (net (code "130") (name "unconnected-(ENC8_-Pad7)") (class "Default")
      (node (ref "ENC8_") (pin "7") (pinfunction "7_7") (pintype "passive"))
    )
    (net (code "131") (name "unconnected-(ENC8_-Pad9)") (class "Default")
      (node (ref "ENC8_") (pin "9") (pinfunction "9_9") (pintype "passive"))
    )
    (net (code "132") (name "unconnected-(ENC8_-Pad10)") (class "Default")
      (node (ref "ENC8_") (pin "10") (pinfunction "10_10") (pintype "passive"))
    )
    (net (code "133") (name "unconnected-(FT232RL-3V3OUT-Pad17)") (class "Default")
      (node (ref "FT232RL") (pin "17") (pinfunction "3V3OUT_17") (pintype "output"))
    )
    (net (code "134") (name "unconnected-(FT232RL-CBUS0-Pad23)") (class "Default")
      (node (ref "FT232RL") (pin "23") (pinfunction "CBUS0_23") (pintype "bidirectional"))
    )
    (net (code "135") (name "unconnected-(FT232RL-CBUS1-Pad22)") (class "Default")
      (node (ref "FT232RL") (pin "22") (pinfunction "CBUS1_22") (pintype "bidirectional"))
    )
    (net (code "136") (name "unconnected-(FT232RL-CBUS2-Pad13)") (class "Default")
      (node (ref "FT232RL") (pin "13") (pinfunction "CBUS2_13") (pintype "bidirectional"))
    )
    (net (code "137") (name "unconnected-(FT232RL-CBUS3-Pad14)") (class "Default")
      (node (ref "FT232RL") (pin "14") (pinfunction "CBUS3_14") (pintype "bidirectional"))
    )
    (net (code "138") (name "unconnected-(FT232RL-CBUS4-Pad12)") (class "Default")
      (node (ref "FT232RL") (pin "12") (pinfunction "CBUS4_12") (pintype "bidirectional"))
    )
    (net (code "139") (name "unconnected-(FT232RL-NC-Pad8)") (class "Default")
      (node (ref "FT232RL") (pin "8") (pinfunction "NC_8") (pintype "no_connect"))
    )
    (net (code "140") (name "unconnected-(FT232RL-NC-Pad24)") (class "Default")
      (node (ref "FT232RL") (pin "24") (pinfunction "NC_24") (pintype "no_connect"))
    )
    (net (code "141") (name "unconnected-(FT232RL-OSCI-Pad27)") (class "Default")
      (node (ref "FT232RL") (pin "27") (pinfunction "OSCI_27") (pintype "input"))
    )
    (net (code "142") (name "unconnected-(FT232RL-OSCO-Pad28)") (class "Default")
      (node (ref "FT232RL") (pin "28") (pinfunction "OSCO_28") (pintype "output"))
    )
    (net (code "143") (name "unconnected-(FT232RL-_CTS-Pad11)") (class "Default")
      (node (ref "FT232RL") (pin "11") (pinfunction "_CTS_11") (pintype "input"))
    )
    (net (code "144") (name "unconnected-(FT232RL-_DCD-Pad10)") (class "Default")
      (node (ref "FT232RL") (pin "10") (pinfunction "_DCD_10") (pintype "input"))
    )
    (net (code "145") (name "unconnected-(FT232RL-_DSR-Pad9)") (class "Default")
      (node (ref "FT232RL") (pin "9") (pinfunction "_DSR_9") (pintype "input"))
    )
    (net (code "146") (name "unconnected-(FT232RL-_DTR-Pad2)") (class "Default")
      (node (ref "FT232RL") (pin "2") (pinfunction "_DTR_2") (pintype "input"))
    )
    (net (code "147") (name "unconnected-(FT232RL-_RESET-Pad19)") (class "Default")
      (node (ref "FT232RL") (pin "19") (pinfunction "_RESET_19") (pintype "input"))
    )
    (net (code "148") (name "unconnected-(FT232RL-_RI-Pad6)") (class "Default")
      (node (ref "FT232RL") (pin "6") (pinfunction "_RI_6") (pintype "input"))
    )
    (net (code "149") (name "unconnected-(FT232RL-_RTS-Pad3)") (class "Default")
      (node (ref "FT232RL") (pin "3") (pinfunction "_RTS_3") (pintype "output"))
    )
    (net (code "150") (name "unconnected-(IC2-ADC6-Pad19)") (class "Default")
      (node (ref "IC2") (pin "19") (pinfunction "ADC6_19") (pintype "passive"))
    )
    (net (code "151") (name "unconnected-(IC2-ADC7-Pad22)") (class "Default")
      (node (ref "IC2") (pin "22") (pinfunction "ADC7_22") (pintype "passive"))
    )
    (net (code "152") (name "unconnected-(IC2-PC0(ADC0{slash}PCINT8)-Pad23)") (class "Default")
      (node (ref "IC2") (pin "23") (pinfunction "PC0(ADC0/PCINT8)_23") (pintype "bidirectional"))
    )
    (net (code "153") (name "unconnected-(IC2-PC1(ADC1{slash}PCINT9)-Pad24)") (class "Default")
      (node (ref "IC2") (pin "24") (pinfunction "PC1(ADC1/PCINT9)_24") (pintype "bidirectional"))
    )
    (net (code "154") (name "unconnected-(IC2-PC2(ADC2{slash}PCINT10)-Pad25)") (class "Default")
      (node (ref "IC2") (pin "25") (pinfunction "PC2(ADC2/PCINT10)_25") (pintype "bidirectional"))
    )
    (net (code "155") (name "unconnected-(IC2-PC3(ADC3{slash}PCINT11)-Pad26)") (class "Default")
      (node (ref "IC2") (pin "26") (pinfunction "PC3(ADC3/PCINT11)_26") (pintype "bidirectional"))
    )
    (net (code "156") (name "unconnected-(IC2-PC4(ADC4{slash}SDA{slash}PCINT12)-Pad27)") (class "Default")
      (node (ref "IC2") (pin "27") (pinfunction "PC4(ADC4/SDA/PCINT12)_27") (pintype "bidirectional"))
    )
    (net (code "157") (name "unconnected-(IC2-PC5(ADC5{slash}SCL{slash}PCINT13)-Pad28)") (class "Default")
      (node (ref "IC2") (pin "28") (pinfunction "PC5(ADC5/SCL/PCINT13)_28") (pintype "bidirectional"))
    )
    (net (code "158") (name "unconnected-(IC2-PD3(INT1{slash}OC2B{slash}PCINT19)-Pad1)") (class "Default")
      (node (ref "IC2") (pin "1") (pinfunction "PD3(INT1/OC2B/PCINT19)_1") (pintype "bidirectional"))
    )
    (net (code "159") (name "unconnected-(IC2-PD4(T0{slash}XCK{slash}PCINT20)-Pad2)") (class "Default")
      (node (ref "IC2") (pin "2") (pinfunction "PD4(T0/XCK/PCINT20)_2") (pintype "bidirectional"))
    )
    (net (code "160") (name "unconnected-(IC2-PD5(T1{slash}OC0B{slash}PCINT21)-Pad9)") (class "Default")
      (node (ref "IC2") (pin "9") (pinfunction "PD5(T1/OC0B/PCINT21)_9") (pintype "bidirectional"))
    )
    (net (code "161") (name "unconnected-(IC2-PD6(AIN0{slash}OC0A{slash}PCINT22)-Pad10)") (class "Default")
      (node (ref "IC2") (pin "10") (pinfunction "PD6(AIN0/OC0A/PCINT22)_10") (pintype "bidirectional"))
    )
    (net (code "162") (name "unconnected-(IC2-PD7(AIN1{slash}PCINT23)-Pad11)") (class "Default")
      (node (ref "IC2") (pin "11") (pinfunction "PD7(AIN1/PCINT23)_11") (pintype "bidirectional"))
    )
    (net (code "163") (name "unconnected-(MPU9150-ES_CL-Pad6)") (class "Default")
      (node (ref "MPU9150") (pin "6") (pinfunction "ES_CL_6") (pintype "bidirectional"))
    )
    (net (code "164") (name "unconnected-(MPU9150-ES_DA-Pad5)") (class "Default")
      (node (ref "MPU9150") (pin "5") (pinfunction "ES_DA_5") (pintype "bidirectional"))
    )
    (net (code "165") (name "unconnected-(MPU9150-FSYNC-Pad7)") (class "Default")
      (node (ref "MPU9150") (pin "7") (pinfunction "FSYNC_7") (pintype "bidirectional"))
    )
    (net (code "166") (name "unconnected-(Q19-GND-Pad2)") (class "Default")
      (node (ref "Q19") (pin "2") (pinfunction "GND_2") (pintype "power_in"))
    )
    (net (code "167") (name "unconnected-(STM32F103VET7A-NC-Pad73)") (class "Default")
      (node (ref "STM32F103VET7") (pin "73") (pinfunction "NC_73") (pintype "no_connect"))
    )
    (net (code "168") (name "unconnected-(STM32F103VET7C-PA8{slash}USART1_CK{slash}TIM1_CH1{slash}MCO-Pad67)") (class "Default")
      (node (ref "STM32F103VET7") (pin "67") (pinfunction "PA8/USART1_CK/TIM1_CH1/MCO_67") (pintype "bidirectional"))
    )
    (net (code "169") (name "unconnected-(STM32F103VET7C-PA11{slash}USART1_CTS{slash}TIM1_CH4{slash}CANRX{slash}USBDM-Pad70)") (class "Default")
      (node (ref "STM32F103VET7") (pin "70") (pinfunction "PA11/USART1_CTS/TIM1_CH4/CANRX/USBDM_70") (pintype "bidirectional"))
    )
    (net (code "170") (name "unconnected-(STM32F103VET7C-PA12{slash}USART1_RTS_TIM1_ETR{slash}CANTX{slash}USBDP-Pad71)") (class "Default")
      (node (ref "STM32F103VET7") (pin "71") (pinfunction "PA12/USART1_RTS_TIM1_ETR/CANTX/USBDP_71") (pintype "bidirectional"))
    )
    (net (code "171") (name "unconnected-(STM32F103VET7D-PA2{slash}USART2_TX{slash}ADC12_IN2{slash}TIM2_CH2-Pad25)") (class "Default")
      (node (ref "STM32F103VET7") (pin "25") (pinfunction "PA2/USART2_TX/ADC12_IN2/TIM2_CH2_25") (pintype "bidirectional"))
    )
    (net (code "172") (name "unconnected-(STM32F103VET7D-PA3{slash}USART2_RX{slash}ADC12_IN3{slash}TIM2_CH4-Pad26)") (class "Default")
      (node (ref "STM32F103VET7") (pin "26") (pinfunction "PA3/USART2_RX/ADC12_IN3/TIM2_CH4_26") (pintype "bidirectional"))
    )
    (net (code "173") (name "unconnected-(STM32F103VET7D-PA4{slash}USART2_CK{slash}ADC12_IN4{slash}SPI1_NSS-Pad29)") (class "Default")
      (node (ref "STM32F103VET7") (pin "29") (pinfunction "PA4/USART2_CK/ADC12_IN4/SPI1_NSS_29") (pintype "bidirectional"))
    )
    (net (code "174") (name "unconnected-(STM32F103VET7E-I2C2_SMBA{slash}USART3_CK{slash}TIM1_BKIN{slash}SPI2_NSS{slash}PB12-Pad51)") (class "Default")
      (node (ref "STM32F103VET7") (pin "51") (pinfunction "I2C2_SMBA/USART3_CK/TIM1_BKIN/SPI2_NSS/PB12_51") (pintype "bidirectional"))
    )
    (net (code "175") (name "unconnected-(STM32F103VET7F-ADC12_IN9{slash}TIM3_CH4{slash}RM-TIM1_CH3N{slash}PB1-Pad36)") (class "Default")
      (node (ref "STM32F103VET7") (pin "36") (pinfunction "ADC12_IN9/TIM3_CH4/RM-TIM1_CH3N/PB1_36") (pintype "bidirectional"))
    )
    (net (code "176") (name "unconnected-(STM32F103VET7F-BOOT1{slash}PB2-Pad37)") (class "Default")
      (node (ref "STM32F103VET7") (pin "37") (pinfunction "BOOT1/PB2_37") (pintype "bidirectional"))
    )
    (net (code "177") (name "unconnected-(STM32F103VET7G-PC13{slash}TAMPER-RTC-Pad7)") (class "Default")
      (node (ref "STM32F103VET7") (pin "7") (pinfunction "PC13/TAMPER-RTC_7") (pintype "bidirectional"))
    )
    (net (code "178") (name "unconnected-(STM32F103VET7G-PC14{slash}OSC32-IN-Pad8)") (class "Default")
      (node (ref "STM32F103VET7") (pin "8") (pinfunction "PC14/OSC32-IN_8") (pintype "bidirectional"))
    )
    (net (code "179") (name "unconnected-(STM32F103VET7G-PC15{slash}OSC32_OUT-Pad9)") (class "Default")
      (node (ref "STM32F103VET7") (pin "9") (pinfunction "PC15/OSC32_OUT_9") (pintype "bidirectional"))
    )
    (net (code "180") (name "unconnected-(STM32F103VET7H-PC0{slash}ADC12_IN10-Pad15)") (class "Default")
      (node (ref "STM32F103VET7") (pin "15") (pinfunction "PC0/ADC12_IN10_15") (pintype "bidirectional"))
    )
    (net (code "181") (name "unconnected-(STM32F103VET7H-PC1{slash}ADC12_IN11-Pad16)") (class "Default")
      (node (ref "STM32F103VET7") (pin "16") (pinfunction "PC1/ADC12_IN11_16") (pintype "bidirectional"))
    )
    (net (code "182") (name "unconnected-(STM32F103VET7H-PC2{slash}ADC12_IN12-Pad17)") (class "Default")
      (node (ref "STM32F103VET7") (pin "17") (pinfunction "PC2/ADC12_IN12_17") (pintype "bidirectional"))
    )
    (net (code "183") (name "unconnected-(STM32F103VET7H-PC3{slash}ADC12_IN13-Pad18)") (class "Default")
      (node (ref "STM32F103VET7") (pin "18") (pinfunction "PC3/ADC12_IN13_18") (pintype "bidirectional"))
    )
    (net (code "184") (name "unconnected-(STM32F103VET7I-RM-TIM4_CH3{slash}PD14-Pad61)") (class "Default")
      (node (ref "STM32F103VET7") (pin "61") (pinfunction "RM-TIM4_CH3/PD14_61") (pintype "bidirectional"))
    )
    (net (code "185") (name "unconnected-(STM32F103VET7I-RM-TIM4_CH4{slash}PD15-Pad62)") (class "Default")
      (node (ref "STM32F103VET7") (pin "62") (pinfunction "RM-TIM4_CH4/PD15_62") (pintype "bidirectional"))
    )
    (net (code "186") (name "unconnected-(STM32F103VET7I-RM-USART3_CTS{slash}PD11-Pad58)") (class "Default")
      (node (ref "STM32F103VET7") (pin "58") (pinfunction "RM-USART3_CTS/PD11_58") (pintype "bidirectional"))
    )
    (net (code "187") (name "unconnected-(STM32F103VET7I-RM-USART3_RX{slash}PD9-Pad56)") (class "Default")
      (node (ref "STM32F103VET7") (pin "56") (pinfunction "RM-USART3_RX/PD9_56") (pintype "bidirectional"))
    )
    (net (code "188") (name "unconnected-(STM32F103VET7I-RM-USART3_TX{slash}PD8-Pad55)") (class "Default")
      (node (ref "STM32F103VET7") (pin "55") (pinfunction "RM-USART3_TX/PD8_55") (pintype "bidirectional"))
    )
    (net (code "189") (name "unconnected-(STM32F103VET7I-RM-USASRT3_CK{slash}PD10-Pad57)") (class "Default")
      (node (ref "STM32F103VET7") (pin "57") (pinfunction "RM-USASRT3_CK/PD10_57") (pintype "bidirectional"))
    )
    (net (code "190") (name "unconnected-(STM32F103VET7J-OSC_OUT{slash}RM-CANTX{slash}PD1-Pad82)") (class "Default")
      (node (ref "STM32F103VET7") (pin "82") (pinfunction "OSC_OUT/RM-CANTX/PD1_82") (pintype "bidirectional"))
    )
    (net (code "191") (name "unconnected-(STM32F103VET7J-USART2_CTS{slash}PD3-Pad84)") (class "Default")
      (node (ref "STM32F103VET7") (pin "84") (pinfunction "USART2_CTS/PD3_84") (pintype "bidirectional"))
    )
    (net (code "192") (name "unconnected-(STM32F103VET7K-PE8{slash}RM-TIM1_CH1N-Pad39)") (class "Default")
      (node (ref "STM32F103VET7") (pin "39") (pinfunction "PE8/RM-TIM1_CH1N_39") (pintype "bidirectional"))
    )
    (net (code "193") (name "unconnected-(STM32F103VET7K-PE10{slash}RM-TIM1_CH2N-Pad41)") (class "Default")
      (node (ref "STM32F103VET7") (pin "41") (pinfunction "PE10/RM-TIM1_CH2N_41") (pintype "bidirectional"))
    )
    (net (code "194") (name "unconnected-(STM32F103VET7K-PE12{slash}RM-TIM1_CH3N-Pad43)") (class "Default")
      (node (ref "STM32F103VET7") (pin "43") (pinfunction "PE12/RM-TIM1_CH3N_43") (pintype "bidirectional"))
    )
    (net (code "195") (name "unconnected-(STM32F103VET7K-PE15{slash}RM-TIM1_CKIN-Pad46)") (class "Default")
      (node (ref "STM32F103VET7") (pin "46") (pinfunction "PE15/RM-TIM1_CKIN_46") (pintype "bidirectional"))
    )
    (net (code "196") (name "unconnected-(STM32F103VET7L-PE3{slash}TRACED0-Pad2)") (class "Default")
      (node (ref "STM32F103VET7") (pin "2") (pinfunction "PE3/TRACED0_2") (pintype "bidirectional"))
    )
    (net (code "197") (name "unconnected-(STM32F103VET7L-PE4{slash}TRACED1-Pad3)") (class "Default")
      (node (ref "STM32F103VET7") (pin "3") (pinfunction "PE4/TRACED1_3") (pintype "bidirectional"))
    )
    (net (code "198") (name "unconnected-(STM32F103VET7L-PE5{slash}TRACED2-Pad4)") (class "Default")
      (node (ref "STM32F103VET7") (pin "4") (pinfunction "PE5/TRACED2_4") (pintype "bidirectional"))
    )
    (net (code "199") (name "unconnected-(STM32F103VET7L-PE6{slash}TRACED3-Pad5)") (class "Default")
      (node (ref "STM32F103VET7") (pin "5") (pinfunction "PE6/TRACED3_5") (pintype "bidirectional"))
    )
    (net (code "200") (name "unconnected-(STM32F103VET7L-PE7{slash}TIM1_ETR-Pad38)") (class "Default")
      (node (ref "STM32F103VET7") (pin "38") (pinfunction "PE7/TIM1_ETR_38") (pintype "bidirectional"))
    )
    (net (code "201") (name "unconnected-(SWD-Pad4)") (class "Default")
      (node (ref "SWD") (pin "4") (pinfunction "4_4") (pintype "passive"))
    )
    (net (code "202") (name "unconnected-(U$1-PadCD1)") (class "Default")
      (node (ref "U$1") (pin "CD1") (pinfunction "CD1_CD1") (pintype "bidirectional"))
    )
    (net (code "203") (name "unconnected-(U$1-PadCD2)") (class "Default")
      (node (ref "U$1") (pin "CD2") (pinfunction "CD2_CD2") (pintype "bidirectional"))
    )
    (net (code "204") (name "unconnected-(U$2-NC-Pad8)") (class "Default")
      (node (ref "U$2") (pin "8") (pinfunction "NC_8") (pintype "bidirectional"))
    )
    (net (code "205") (name "unconnected-(U$2-NC{slash}2-Pad11)") (class "Default")
      (node (ref "U$2") (pin "11") (pinfunction "NC/2_11") (pintype "bidirectional"))
    )
    (net (code "206") (name "unconnected-(U$2-NC{slash}3-Pad12)") (class "Default")
      (node (ref "U$2") (pin "12") (pinfunction "NC/3_12") (pintype "bidirectional"))
    )
    (net (code "207") (name "unconnected-(U$2-PGOOD-Pad10)") (class "Default")
      (node (ref "U$2") (pin "10") (pinfunction "PGOOD_10") (pintype "bidirectional"))
    )
    (net (code "208") (name "unconnected-(U$2-SEQ-Pad9)") (class "Default")
      (node (ref "U$2") (pin "9") (pinfunction "SEQ_9") (pintype "bidirectional"))
    )
    (net (code "209") (name "unconnected-(U$8A-VREF-Pad5)") (class "Default")
      (node (ref "U$8") (pin "5") (pinfunction "VREF_5") (pintype "bidirectional"))
    )
    (net (code "210") (name "unconnected-(U2-GOUT0-Pad4)") (class "Default")
      (node (ref "U2") (pin "4") (pinfunction "GOUT0_4") (pintype "bidirectional"))
    )
    (net (code "211") (name "unconnected-(U2-GOUT1-Pad5)") (class "Default")
      (node (ref "U2") (pin "5") (pinfunction "GOUT1_5") (pintype "bidirectional"))
    )
    (net (code "212") (name "unconnected-(U2-GOUT2-Pad6)") (class "Default")
      (node (ref "U2") (pin "6") (pinfunction "GOUT2_6") (pintype "bidirectional"))
    )
    (net (code "213") (name "unconnected-(U2-GOUT3-Pad7)") (class "Default")
      (node (ref "U2") (pin "7") (pinfunction "GOUT3_7") (pintype "bidirectional"))
    )
    (net (code "214") (name "unconnected-(U2-GOUT4-Pad8)") (class "Default")
      (node (ref "U2") (pin "8") (pinfunction "GOUT4_8") (pintype "bidirectional"))
    )
    (net (code "215") (name "unconnected-(U2-GOUT5-Pad9)") (class "Default")
      (node (ref "U2") (pin "9") (pinfunction "GOUT5_9") (pintype "bidirectional"))
    )
    (net (code "216") (name "unconnected-(U2-GOUT6-Pad10)") (class "Default")
      (node (ref "U2") (pin "10") (pinfunction "GOUT6_10") (pintype "bidirectional"))
    )
    (net (code "217") (name "unconnected-(U2-GOUT7-Pad11)") (class "Default")
      (node (ref "U2") (pin "11") (pinfunction "GOUT7_11") (pintype "bidirectional"))
    )
    (net (code "218") (name "unconnected-(U2-GPIN0-Pad26)") (class "Default")
      (node (ref "U2") (pin "26") (pinfunction "GPIN0_26") (pintype "bidirectional"))
    )
    (net (code "219") (name "unconnected-(U2-GPIN1-Pad27)") (class "Default")
      (node (ref "U2") (pin "27") (pinfunction "GPIN1_27") (pintype "bidirectional"))
    )
    (net (code "220") (name "unconnected-(U2-GPIN2-Pad28)") (class "Default")
      (node (ref "U2") (pin "28") (pinfunction "GPIN2_28") (pintype "bidirectional"))
    )
    (net (code "221") (name "unconnected-(U2-GPIN3-Pad29)") (class "Default")
      (node (ref "U2") (pin "29") (pinfunction "GPIN3_29") (pintype "bidirectional"))
    )
    (net (code "222") (name "unconnected-(U2-GPIN4-Pad30)") (class "Default")
      (node (ref "U2") (pin "30") (pinfunction "GPIN4_30") (pintype "bidirectional"))
    )
    (net (code "223") (name "unconnected-(U2-GPIN5-Pad31)") (class "Default")
      (node (ref "U2") (pin "31") (pinfunction "GPIN5_31") (pintype "bidirectional"))
    )
    (net (code "224") (name "unconnected-(U2-GPIN6-Pad32)") (class "Default")
      (node (ref "U2") (pin "32") (pinfunction "GPIN6_32") (pintype "bidirectional"))
    )
    (net (code "225") (name "unconnected-(U2-GPIN7-Pad1)") (class "Default")
      (node (ref "U2") (pin "1") (pinfunction "GPIN7_1") (pintype "bidirectional"))
    )
    (net (code "226") (name "unconnected-(X1-Pad4)") (class "Default")
      (node (ref "X1") (pin "4") (pinfunction "4_4") (pintype "input"))
    )
    (net (code "227") (name "unconnected-(XB1-AD0{slash}DIO0-Pad20)") (class "Default")
      (node (ref "XB1") (pin "20") (pinfunction "AD0/DIO0_20") (pintype "bidirectional"))
    )
    (net (code "228") (name "unconnected-(XB1-AD1{slash}DIO1-Pad19)") (class "Default")
      (node (ref "XB1") (pin "19") (pinfunction "AD1/DIO1_19") (pintype "bidirectional"))
    )
    (net (code "229") (name "unconnected-(XB1-AD2{slash}DIO2-Pad18)") (class "Default")
      (node (ref "XB1") (pin "18") (pinfunction "AD2/DIO2_18") (pintype "bidirectional"))
    )
    (net (code "230") (name "unconnected-(XB1-ASSOC{slash}AD5{slash}DIO5-Pad15)") (class "Default")
      (node (ref "XB1") (pin "15") (pinfunction "ASSOC/AD5/DIO5_15") (pintype "bidirectional"))
    )
    (net (code "231") (name "unconnected-(XB1-CD{slash}DOUT_EN{slash}DO8-Pad4)") (class "Default")
      (node (ref "XB1") (pin "4") (pinfunction "CD/DOUT_EN/DO8_4") (pintype "output"))
    )
    (net (code "232") (name "unconnected-(XB1-COORD_SEL{slash}AD3{slash}DIO3-Pad17)") (class "Default")
      (node (ref "XB1") (pin "17") (pinfunction "COORD_SEL/AD3/DIO3_17") (pintype "bidirectional"))
    )
    (net (code "233") (name "unconnected-(XB1-ON{slash}~{SLEEP}-Pad13)") (class "Default")
      (node (ref "XB1") (pin "13") (pinfunction "ON/~{SLEEP}_13") (pintype "output"))
    )
    (net (code "234") (name "unconnected-(XB1-PWM0{slash}RSSI-Pad6)") (class "Default")
      (node (ref "XB1") (pin "6") (pinfunction "PWM0/RSSI_6") (pintype "output"))
    )
    (net (code "235") (name "unconnected-(XB1-RF_TX{slash}AD4{slash}DIO4-Pad11)") (class "Default")
      (node (ref "XB1") (pin "11") (pinfunction "RF_TX/AD4/DIO4_11") (pintype "bidirectional"))
    )
    (net (code "236") (name "unconnected-(XB1-VREF-Pad14)") (class "Default")
      (node (ref "XB1") (pin "14") (pinfunction "VREF_14") (pintype "input"))
    )
    (net (code "237") (name "unconnected-(XB1-~{CTS}{slash}DIO7-Pad12)") (class "Default")
      (node (ref "XB1") (pin "12") (pinfunction "~{CTS}/DIO7_12") (pintype "bidirectional"))
    )
    (net (code "238") (name "unconnected-(XB1-~{DTR}{slash}SLEEP_RQ{slash}DI8-Pad9)") (class "Default")
      (node (ref "XB1") (pin "9") (pinfunction "~{DTR}/SLEEP_RQ/DI8_9") (pintype "bidirectional"))
    )
    (net (code "239") (name "unconnected-(XB1-~{RESET}-Pad5)") (class "Default")
      (node (ref "XB1") (pin "5") (pinfunction "~{RESET}_5") (pintype "input"))
    )
    (net (code "240") (name "unconnected-(XB1-~{RTS}{slash}AD6{slash}DIO6-Pad16)") (class "Default")
      (node (ref "XB1") (pin "16") (pinfunction "~{RTS}/AD6/DIO6_16") (pintype "bidirectional"))
    )
  )
)
